# elasticNode.net
KiCad netlist of a schematic drawn in EAGLE
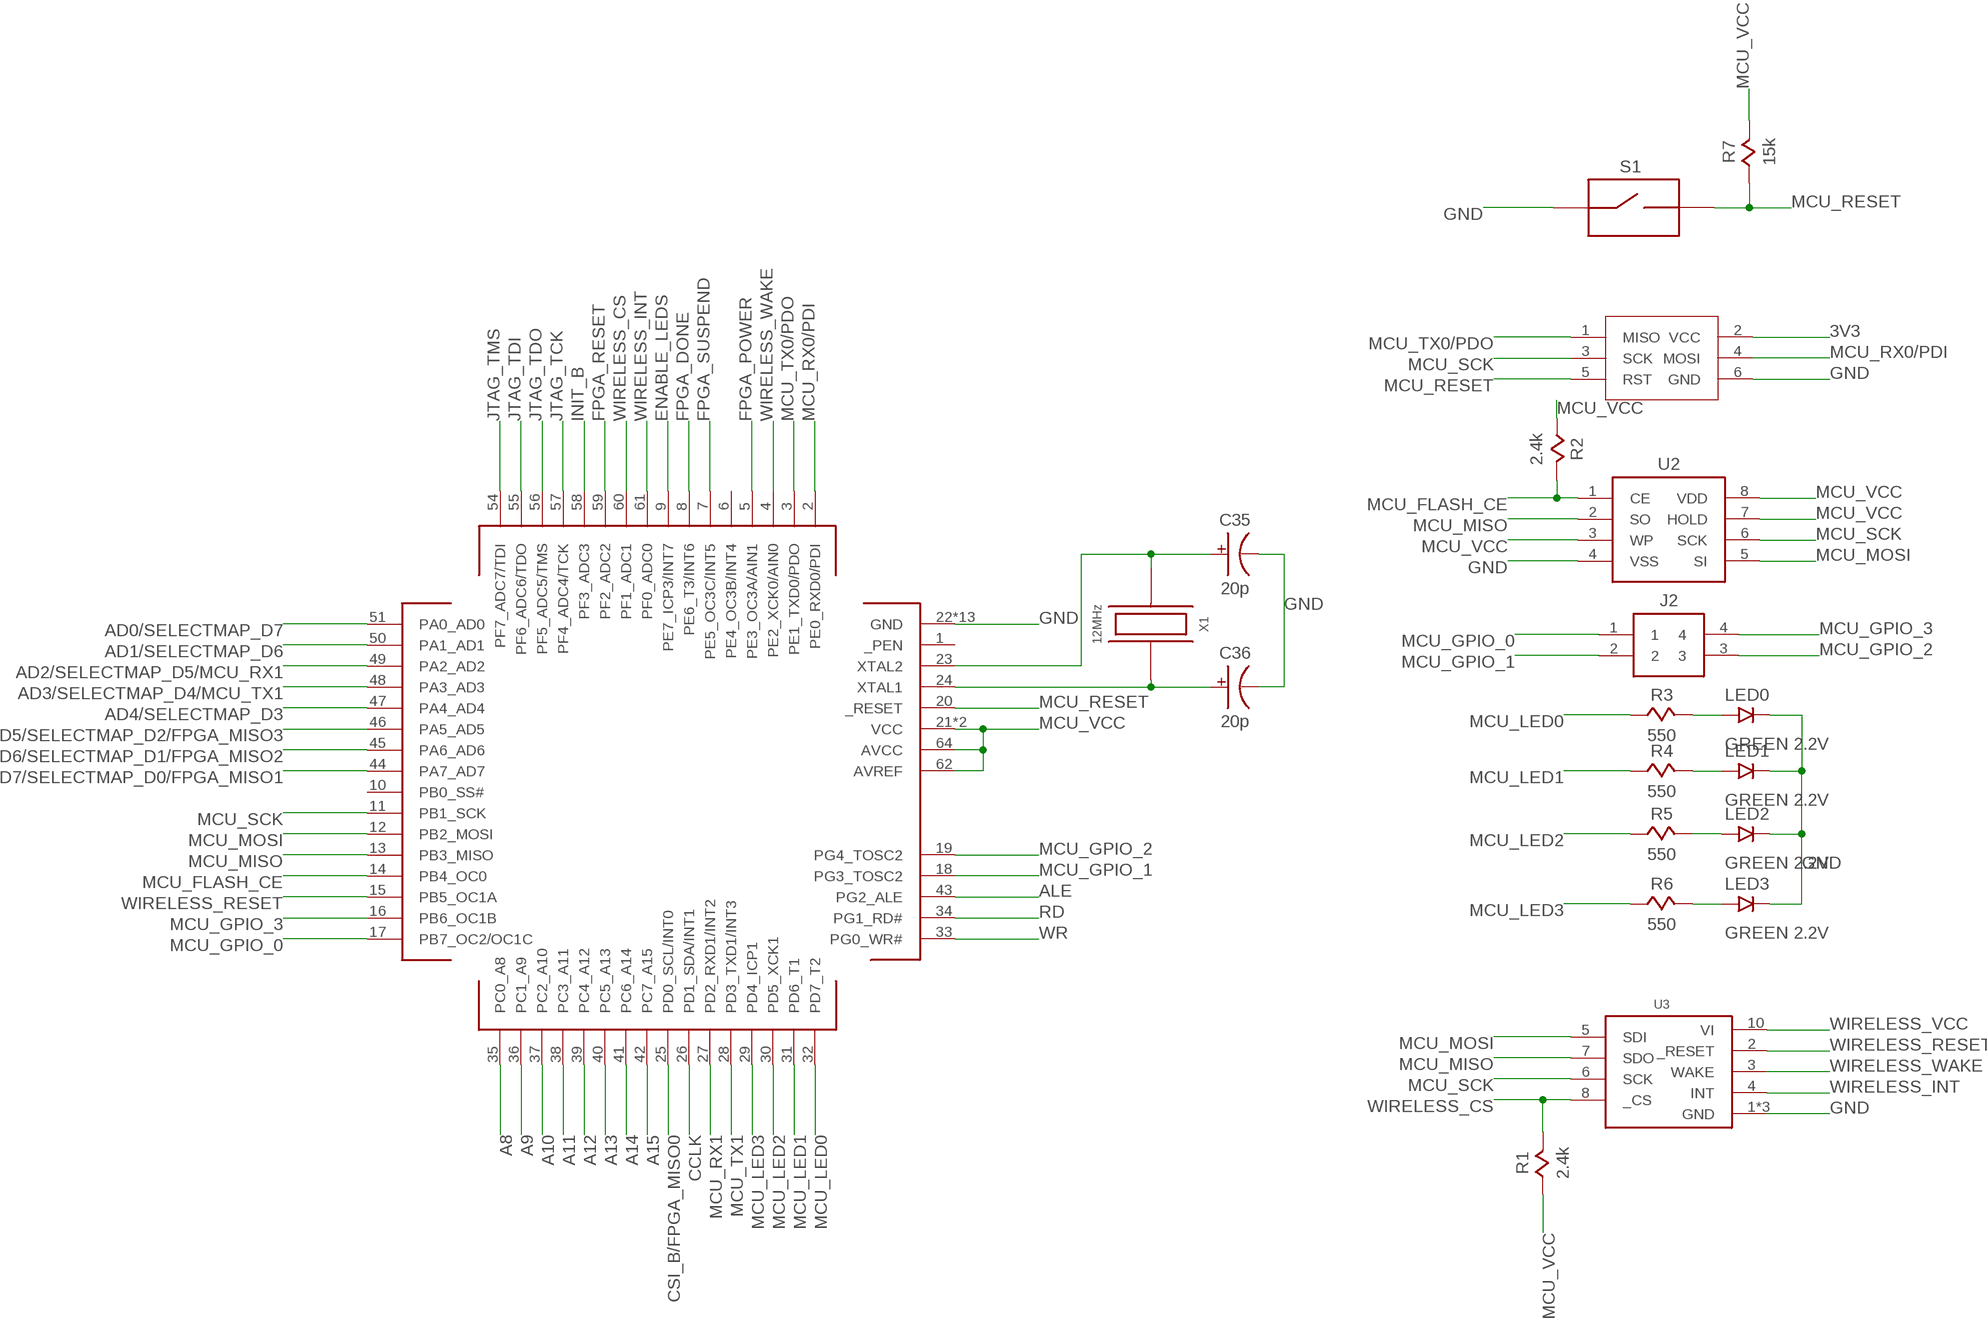
[diagram p0: schematic, sheet 1]
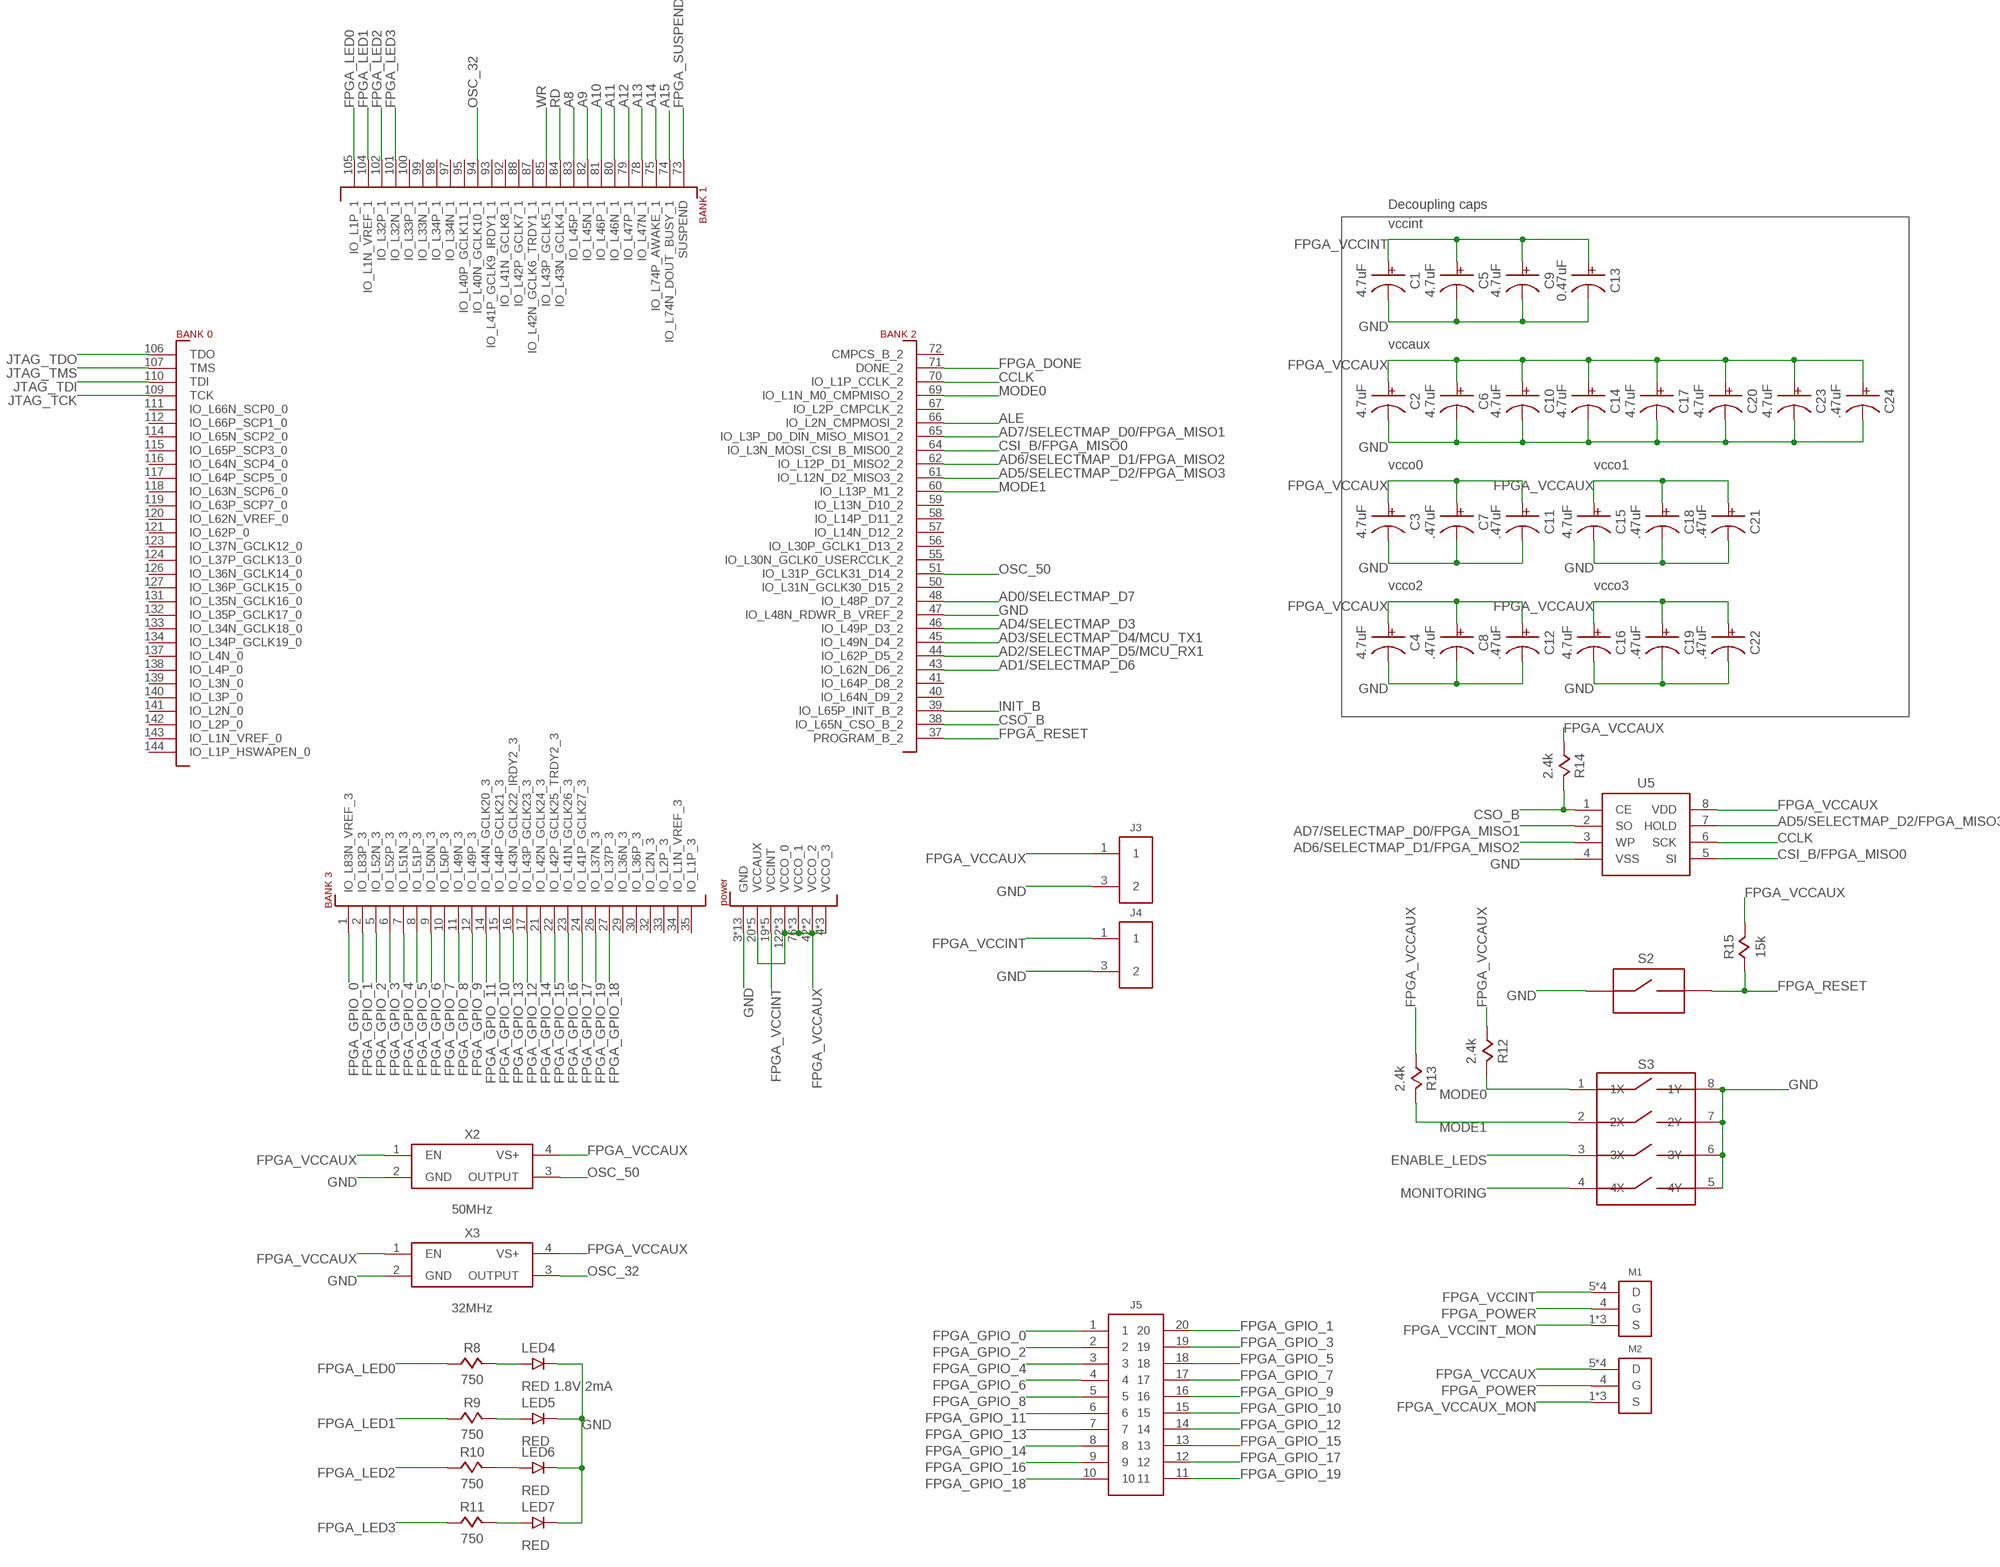
[diagram p1: schematic, sheet 2]
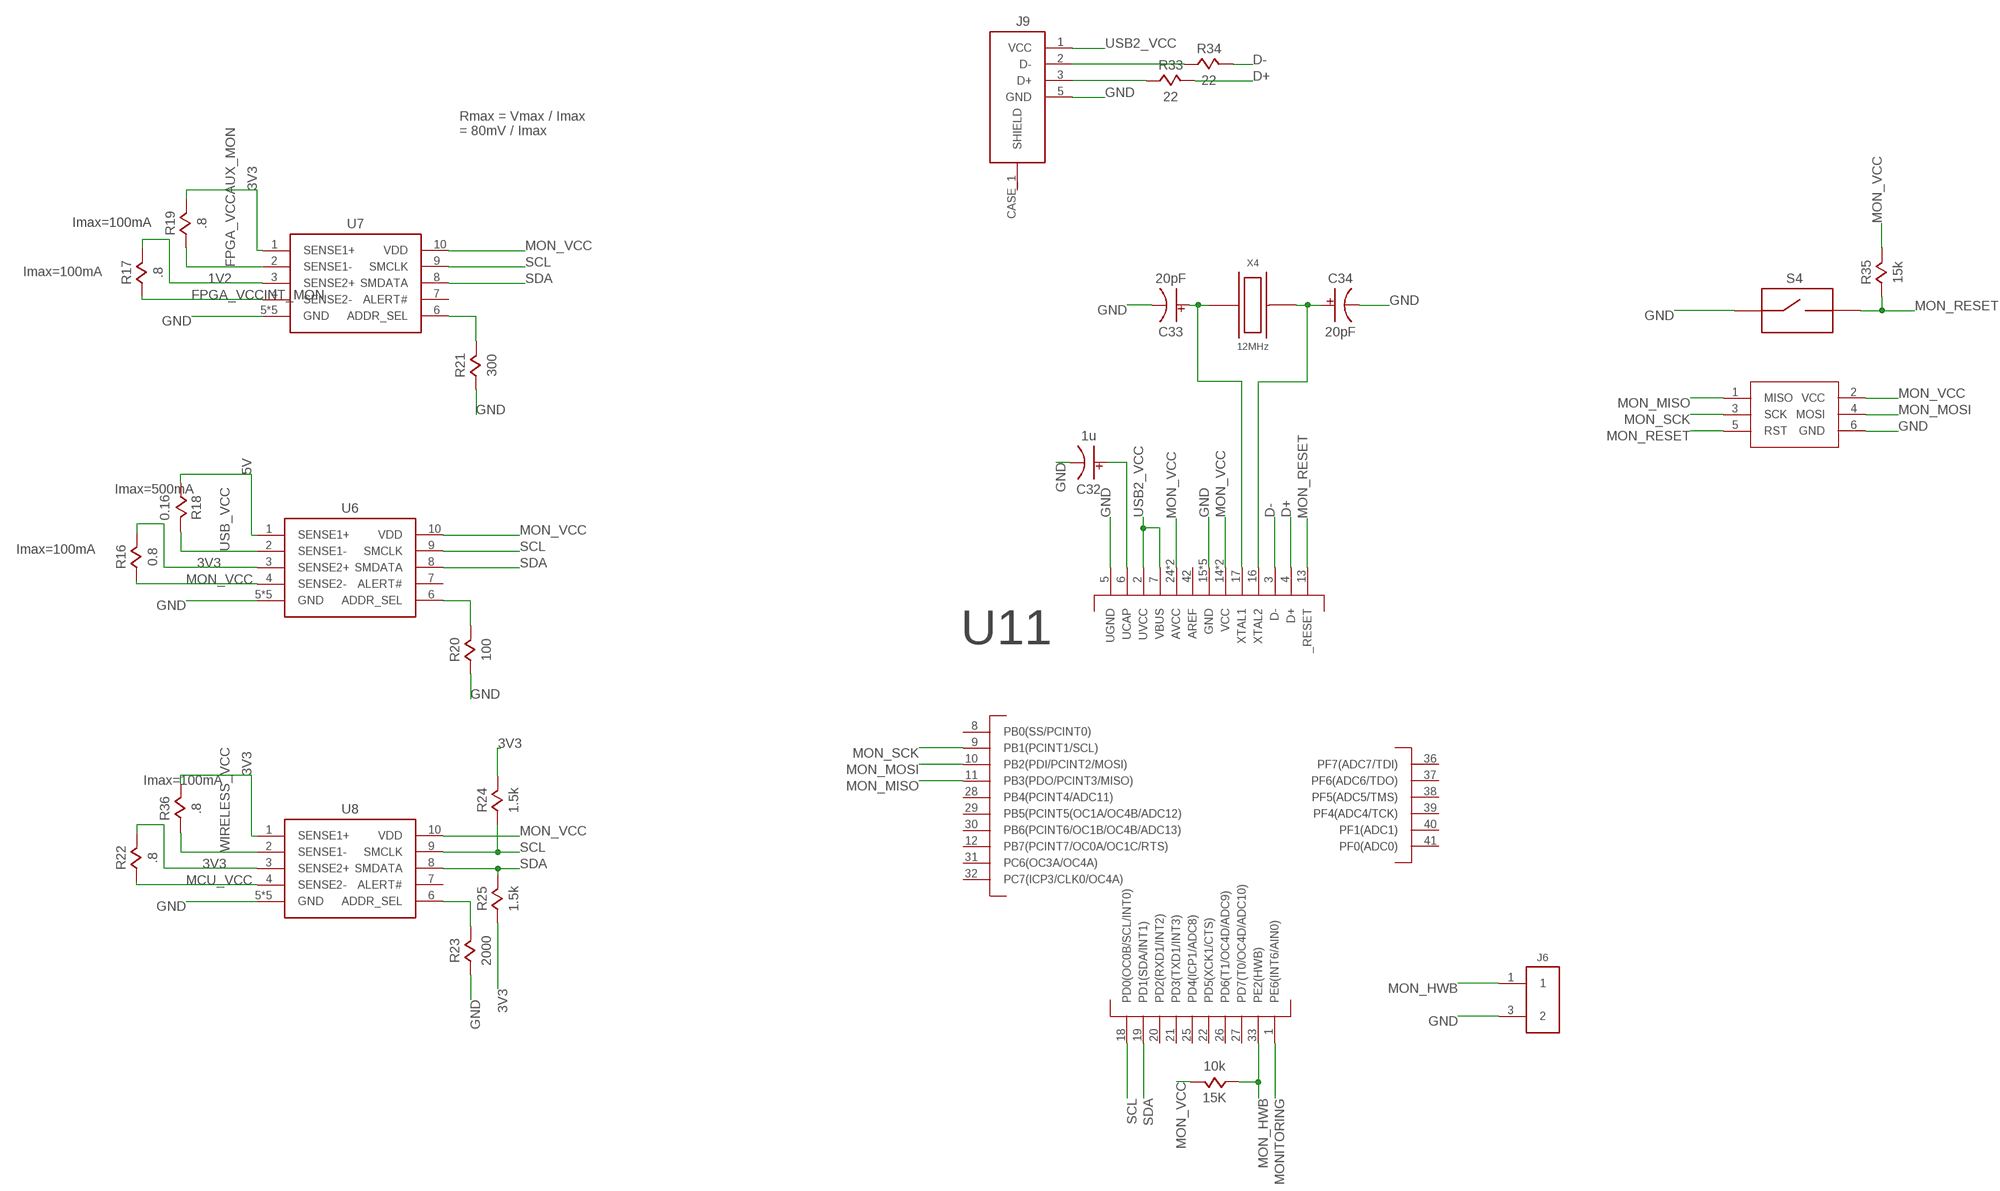
[diagram p2: schematic, sheet 3]
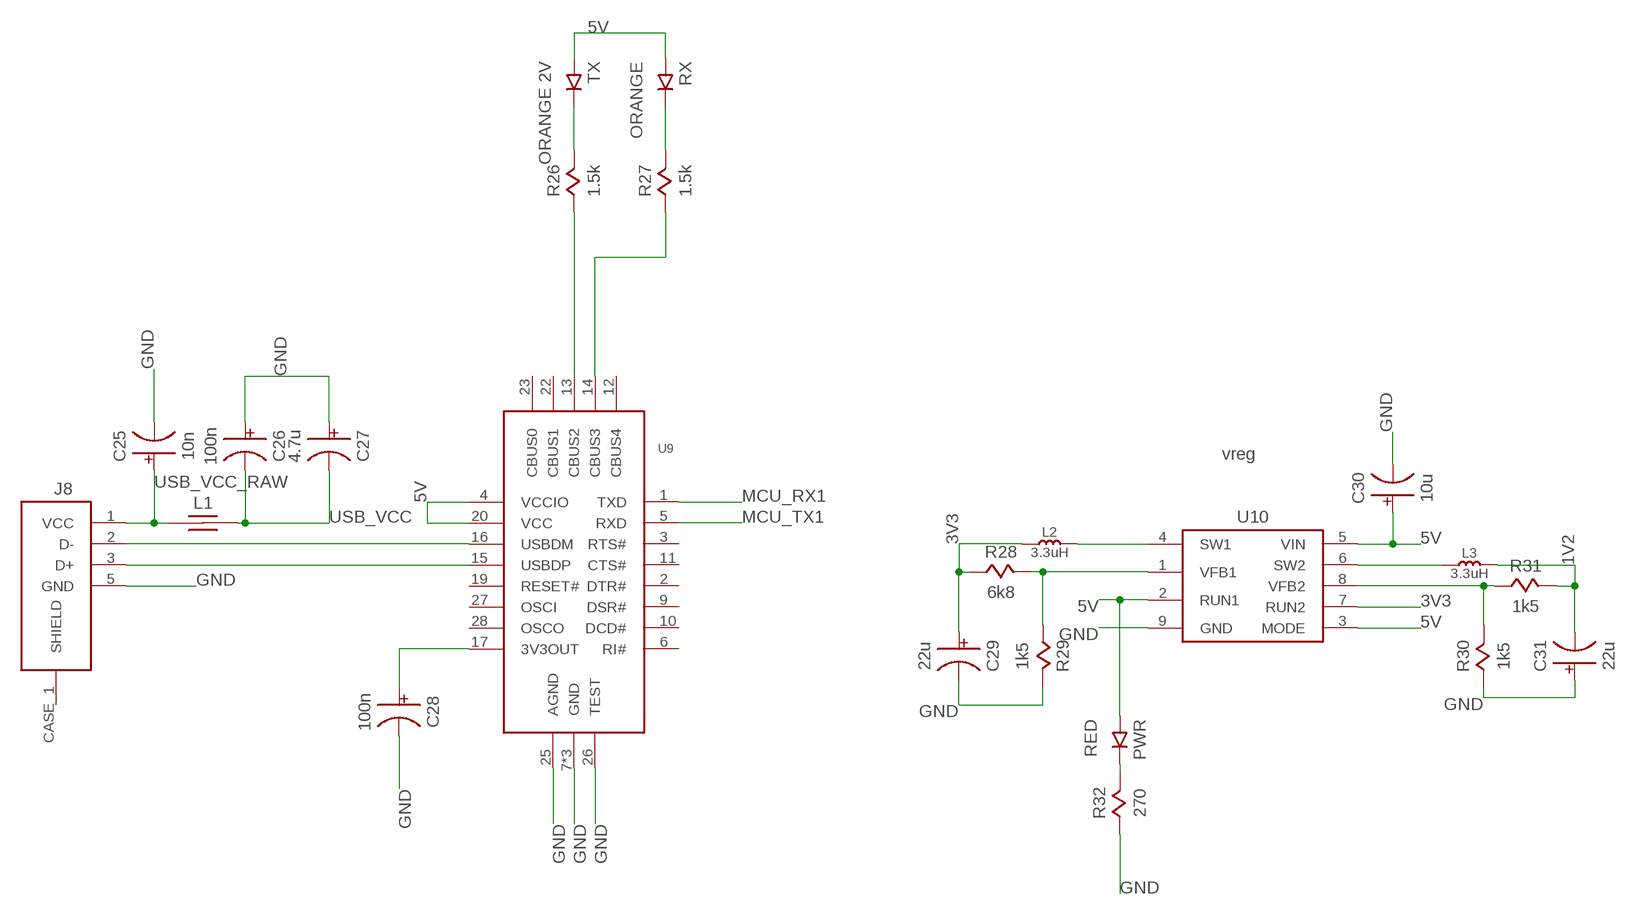
[diagram p3: schematic, sheet 4]

(export (version "E")
  (design (tool "Eeschema 10.0.6"))
  (components
    (comp (ref "15K")
      (value "10k")
      (footprint "eagle-import:0805")
      (libsource (lib "eagle-import") (part "RESISTOR"))
    )
    (comp (ref "C32")
      (value "1u")
      (footprint "eagle-import:0805")
      (libsource (lib "eagle-import") (part "CAPACITOR0805"))
    )
    (comp (ref "C33")
      (value "20pF")
      (footprint "eagle-import:0805")
      (libsource (lib "eagle-import") (part "CAPACITOR0805"))
    )
    (comp (ref "C34")
      (value "20pF")
      (footprint "eagle-import:0805")
      (libsource (lib "eagle-import") (part "CAPACITOR0805"))
    )
    (comp (ref "J6")
      (value "FEMALE_HEADER_2X1")
      (footprint "eagle-import:2X1_HEADER")
      (libsource (lib "eagle-import") (part "FEMALE_HEADER_2X1"))
    )
    (comp (ref "J9")
      (value "USB_CONNSMT")
      (footprint "eagle-import:USB_MICRO_B_SMT")
      (libsource (lib "eagle-import") (part "USB_CONNSMT"))
    )
    (comp (ref "J10")
      (value "ISP_CONN_6PIN")
      (footprint "eagle-import:3X2_HEADER_SMT")
      (libsource (lib "eagle-import") (part "ISP_CONN_6PIN"))
    )
    (comp (ref "R16")
      (value "0.8")
      (footprint "eagle-import:0805")
      (libsource (lib "eagle-import") (part "RESISTOR"))
    )
    (comp (ref "R17")
      (value ".8")
      (footprint "eagle-import:0805")
      (libsource (lib "eagle-import") (part "RESISTOR"))
    )
    (comp (ref "R18")
      (value "0.16")
      (footprint "eagle-import:0805")
      (libsource (lib "eagle-import") (part "RESISTOR"))
    )
    (comp (ref "R19")
      (value ".8")
      (footprint "eagle-import:0805")
      (libsource (lib "eagle-import") (part "RESISTOR"))
    )
    (comp (ref "R20")
      (value "100")
      (footprint "eagle-import:0805")
      (libsource (lib "eagle-import") (part "RESISTOR"))
    )
    (comp (ref "R21")
      (value "300")
      (footprint "eagle-import:0805")
      (libsource (lib "eagle-import") (part "RESISTOR"))
    )
    (comp (ref "R22")
      (value ".8")
      (footprint "eagle-import:0805")
      (libsource (lib "eagle-import") (part "RESISTOR"))
    )
    (comp (ref "R23")
      (value "2000")
      (footprint "eagle-import:0805")
      (libsource (lib "eagle-import") (part "RESISTOR"))
    )
    (comp (ref "R24")
      (value "1.5k")
      (footprint "eagle-import:0805")
      (libsource (lib "eagle-import") (part "RESISTOR"))
    )
    (comp (ref "R25")
      (value "1.5k")
      (footprint "eagle-import:0805")
      (libsource (lib "eagle-import") (part "RESISTOR"))
    )
    (comp (ref "R33")
      (value "22")
      (footprint "eagle-import:0805")
      (libsource (lib "eagle-import") (part "RESISTOR"))
    )
    (comp (ref "R34")
      (value "22")
      (footprint "eagle-import:0805")
      (libsource (lib "eagle-import") (part "RESISTOR"))
    )
    (comp (ref "R35")
      (value "15k")
      (footprint "eagle-import:0805")
      (libsource (lib "eagle-import") (part "RESISTOR"))
    )
    (comp (ref "R36")
      (value ".8")
      (footprint "eagle-import:0805")
      (libsource (lib "eagle-import") (part "RESISTOR"))
    )
    (comp (ref "S4")
      (value "SPST_BUTTON2PIN_SMT")
      (footprint "eagle-import:SPST_2PIN_SMT")
      (libsource (lib "eagle-import") (part "SPST_BUTTON2PIN_SMT"))
    )
    (comp (ref "U6")
      (value "PAC1720")
      (footprint "eagle-import:VDFN10")
      (libsource (lib "eagle-import") (part "PAC1720"))
    )
    (comp (ref "U7")
      (value "PAC1720")
      (footprint "eagle-import:VDFN10")
      (libsource (lib "eagle-import") (part "PAC1720"))
    )
    (comp (ref "U8")
      (value "PAC1720")
      (footprint "eagle-import:VDFN10")
      (libsource (lib "eagle-import") (part "PAC1720"))
    )
    (comp (ref "U11")
      (value "ATMEGA32U4")
      (footprint "eagle-import:QFN44")
      (libsource (lib "eagle-import") (part "ATMEGA32U4"))
    )
    (comp (ref "X4")
      (value "12MHz")
      (footprint "eagle-import:3.2X2.5_OSC")
      (libsource (lib "eagle-import") (part "QUARTZ"))
    )
    (comp (ref "C35")
      (value "20p")
      (footprint "eagle-import:0805")
      (libsource (lib "eagle-import") (part "CAPACITOR0805"))
    )
    (comp (ref "C36")
      (value "20p")
      (footprint "eagle-import:0805")
      (libsource (lib "eagle-import") (part "CAPACITOR0805"))
    )
    (comp (ref "J1")
      (value "ISP_CONN_6PIN")
      (footprint "eagle-import:3X2_HEADER_SMT")
      (fields (field (name "SPICEPREFIX") "X"))
      (libsource (lib "eagle-import") (part "ISP_CONN_6PIN"))
    )
    (comp (ref "J2")
      (value "FEMALE_HEADER_2X2")
      (footprint "eagle-import:2X2_HEADER")
      (libsource (lib "eagle-import") (part "FEMALE_HEADER_2X2"))
    )
    (comp (ref "LED0")
      (value "GREEN 2.2V")
      (footprint "eagle-import:0805")
      (libsource (lib "eagle-import") (part "LED"))
    )
    (comp (ref "LED1")
      (value "GREEN 2.2V")
      (footprint "eagle-import:0805")
      (libsource (lib "eagle-import") (part "LED"))
    )
    (comp (ref "LED2")
      (value "GREEN 2.2V")
      (footprint "eagle-import:0805")
      (libsource (lib "eagle-import") (part "LED"))
    )
    (comp (ref "LED3")
      (value "GREEN 2.2V")
      (footprint "eagle-import:0805")
      (libsource (lib "eagle-import") (part "LED"))
    )
    (comp (ref "R1")
      (value "2.4k")
      (footprint "eagle-import:0805")
      (libsource (lib "eagle-import") (part "RESISTOR"))
    )
    (comp (ref "R2")
      (value "2.4k")
      (footprint "eagle-import:0805")
      (libsource (lib "eagle-import") (part "RESISTOR"))
    )
    (comp (ref "R3")
      (value "550")
      (footprint "eagle-import:0805")
      (libsource (lib "eagle-import") (part "RESISTOR"))
    )
    (comp (ref "R4")
      (value "550")
      (footprint "eagle-import:0805")
      (libsource (lib "eagle-import") (part "RESISTOR"))
    )
    (comp (ref "R5")
      (value "550")
      (footprint "eagle-import:0805")
      (libsource (lib "eagle-import") (part "RESISTOR"))
    )
    (comp (ref "R6")
      (value "550")
      (footprint "eagle-import:0805")
      (libsource (lib "eagle-import") (part "RESISTOR"))
    )
    (comp (ref "R7")
      (value "15k")
      (footprint "eagle-import:0805")
      (libsource (lib "eagle-import") (part "RESISTOR"))
    )
    (comp (ref "S1")
      (value "SPST_BUTTON2PIN_SMT")
      (footprint "eagle-import:SPST_2PIN_SMT")
      (libsource (lib "eagle-import") (part "SPST_BUTTON2PIN_SMT"))
    )
    (comp (ref "U1")
      (value "ATMEGA64AQFN")
      (footprint "eagle-import:QFN64")
      (libsource (lib "eagle-import") (part "ATMEGA64AQFN"))
    )
    (comp (ref "U2")
      (value "SST26VF032B")
      (footprint "eagle-import:SOIC8")
      (libsource (lib "eagle-import") (part "SST26VF032B"))
    )
    (comp (ref "U3")
      (value "MRF24J40MA")
      (footprint "eagle-import:MRF24J40MA")
      (libsource (lib "eagle-import") (part "MRF24J40MA"))
    )
    (comp (ref "X1")
      (value "12MHz")
      (footprint "eagle-import:3.2X2.5_OSC")
      (libsource (lib "eagle-import") (part "QUARTZ"))
    )
    (comp (ref "C25")
      (value "10n")
      (footprint "eagle-import:0805")
      (libsource (lib "eagle-import") (part "CAPACITOR0805"))
    )
    (comp (ref "C26")
      (value "100n")
      (footprint "eagle-import:0805")
      (libsource (lib "eagle-import") (part "CAPACITOR0805"))
    )
    (comp (ref "C27")
      (value "4.7u")
      (footprint "eagle-import:0805")
      (libsource (lib "eagle-import") (part "CAPACITOR0805"))
    )
    (comp (ref "C28")
      (value "100n")
      (footprint "eagle-import:0805")
      (libsource (lib "eagle-import") (part "CAPACITOR0805"))
    )
    (comp (ref "C29")
      (value "22u")
      (footprint "eagle-import:0805")
      (libsource (lib "eagle-import") (part "CAPACITOR0805"))
    )
    (comp (ref "C30")
      (value "10u")
      (footprint "eagle-import:0805")
      (libsource (lib "eagle-import") (part "CAPACITOR0805"))
    )
    (comp (ref "C31")
      (value "22u")
      (footprint "eagle-import:0805")
      (libsource (lib "eagle-import") (part "CAPACITOR0805"))
    )
    (comp (ref "J8")
      (value "USB_CONNSMT")
      (footprint "eagle-import:USB_MICRO_B_SMT")
      (libsource (lib "eagle-import") (part "USB_CONNSMT"))
    )
    (comp (ref "L1")
      (value "40Ohm 1.5A")
      (footprint "eagle-import:0805")
      (libsource (lib "eagle-import") (part "FERRITE_BEAD"))
    )
    (comp (ref "L2")
      (value "3.3uH")
      (footprint "eagle-import:0805")
      (libsource (lib "eagle-import") (part "INDUCTOR"))
    )
    (comp (ref "L3")
      (value "3.3uH")
      (footprint "eagle-import:0805")
      (libsource (lib "eagle-import") (part "INDUCTOR"))
    )
    (comp (ref "PWR")
      (value "RED")
      (footprint "eagle-import:0805")
      (libsource (lib "eagle-import") (part "LED"))
    )
    (comp (ref "R26")
      (value "1.5k")
      (footprint "eagle-import:0805")
      (libsource (lib "eagle-import") (part "RESISTOR"))
    )
    (comp (ref "R27")
      (value "1.5k")
      (footprint "eagle-import:0805")
      (libsource (lib "eagle-import") (part "RESISTOR"))
    )
    (comp (ref "R28")
      (value "6k8")
      (footprint "eagle-import:0805")
      (libsource (lib "eagle-import") (part "RESISTOR"))
    )
    (comp (ref "R29")
      (value "1k5")
      (footprint "eagle-import:0805")
      (libsource (lib "eagle-import") (part "RESISTOR"))
    )
    (comp (ref "R30")
      (value "1k5")
      (footprint "eagle-import:0805")
      (libsource (lib "eagle-import") (part "RESISTOR"))
    )
    (comp (ref "R31")
      (value "1k5")
      (footprint "eagle-import:0805")
      (libsource (lib "eagle-import") (part "RESISTOR"))
    )
    (comp (ref "R32")
      (value "270")
      (footprint "eagle-import:0805")
      (libsource (lib "eagle-import") (part "RESISTOR"))
    )
    (comp (ref "RX")
      (value "ORANGE")
      (footprint "eagle-import:0805")
      (libsource (lib "eagle-import") (part "LED"))
    )
    (comp (ref "TX")
      (value "ORANGE 2V")
      (footprint "eagle-import:0805")
      (libsource (lib "eagle-import") (part "LED"))
    )
    (comp (ref "U9")
      (value "FT232RSSOP28")
      (footprint "eagle-import:SSOP28")
      (libsource (lib "eagle-import") (part "FT232RSSOP28"))
    )
    (comp (ref "U10")
      (value "LTC3419DFN")
      (footprint "eagle-import:DFN8")
      (libsource (lib "eagle-import") (part "LTC3419DFN"))
    )
    (comp (ref "C1")
      (value "4.7uF")
      (footprint "eagle-import:0805")
      (libsource (lib "eagle-import") (part "CAPACITOR0805"))
    )
    (comp (ref "C2")
      (value "4.7uF")
      (footprint "eagle-import:0805")
      (libsource (lib "eagle-import") (part "CAPACITOR0805"))
    )
    (comp (ref "C3")
      (value "4.7uF")
      (footprint "eagle-import:0805")
      (libsource (lib "eagle-import") (part "CAPACITOR0805"))
    )
    (comp (ref "C4")
      (value "4.7uF")
      (footprint "eagle-import:0805")
      (libsource (lib "eagle-import") (part "CAPACITOR0805"))
    )
    (comp (ref "C5")
      (value "4.7uF")
      (footprint "eagle-import:0805")
      (libsource (lib "eagle-import") (part "CAPACITOR0805"))
    )
    (comp (ref "C6")
      (value "4.7uF")
      (footprint "eagle-import:0805")
      (libsource (lib "eagle-import") (part "CAPACITOR0805"))
    )
    (comp (ref "C7")
      (value ".47uF")
      (footprint "eagle-import:0402")
      (libsource (lib "eagle-import") (part "CAPACITOR0402"))
    )
    (comp (ref "C8")
      (value ".47uF")
      (footprint "eagle-import:0402")
      (libsource (lib "eagle-import") (part "CAPACITOR0402"))
    )
    (comp (ref "C9")
      (value "4.7uF")
      (footprint "eagle-import:0805")
      (libsource (lib "eagle-import") (part "CAPACITOR0805"))
    )
    (comp (ref "C10")
      (value "4.7uF")
      (footprint "eagle-import:0805")
      (libsource (lib "eagle-import") (part "CAPACITOR0805"))
    )
    (comp (ref "C11")
      (value ".47uF")
      (footprint "eagle-import:0402")
      (libsource (lib "eagle-import") (part "CAPACITOR0402"))
    )
    (comp (ref "C12")
      (value ".47uF")
      (footprint "eagle-import:0402")
      (libsource (lib "eagle-import") (part "CAPACITOR0402"))
    )
    (comp (ref "C13")
      (value "0.47uF")
      (footprint "eagle-import:0402")
      (libsource (lib "eagle-import") (part "CAPACITOR0402"))
    )
    (comp (ref "C14")
      (value "4.7uF")
      (footprint "eagle-import:0805")
      (libsource (lib "eagle-import") (part "CAPACITOR0805"))
    )
    (comp (ref "C15")
      (value "4.7uF")
      (footprint "eagle-import:0805")
      (libsource (lib "eagle-import") (part "CAPACITOR0805"))
    )
    (comp (ref "C16")
      (value "4.7uF")
      (footprint "eagle-import:0805")
      (libsource (lib "eagle-import") (part "CAPACITOR0805"))
    )
    (comp (ref "C17")
      (value "4.7uF")
      (footprint "eagle-import:0805")
      (libsource (lib "eagle-import") (part "CAPACITOR0805"))
    )
    (comp (ref "C18")
      (value ".47uF")
      (footprint "eagle-import:0402")
      (libsource (lib "eagle-import") (part "CAPACITOR0402"))
    )
    (comp (ref "C19")
      (value ".47uF")
      (footprint "eagle-import:0402")
      (libsource (lib "eagle-import") (part "CAPACITOR0402"))
    )
    (comp (ref "C20")
      (value "4.7uF")
      (footprint "eagle-import:0805")
      (libsource (lib "eagle-import") (part "CAPACITOR0805"))
    )
    (comp (ref "C21")
      (value ".47uF")
      (footprint "eagle-import:0402")
      (libsource (lib "eagle-import") (part "CAPACITOR0402"))
    )
    (comp (ref "C22")
      (value ".47uF")
      (footprint "eagle-import:0402")
      (libsource (lib "eagle-import") (part "CAPACITOR0402"))
    )
    (comp (ref "C23")
      (value "4.7uF")
      (footprint "eagle-import:0805")
      (libsource (lib "eagle-import") (part "CAPACITOR0805"))
    )
    (comp (ref "C24")
      (value ".47uF")
      (footprint "eagle-import:0805")
      (libsource (lib "eagle-import") (part "CAPACITOR0805"))
    )
    (comp (ref "J3")
      (value "FEMALE_HEADER_2X1")
      (footprint "eagle-import:2X1_HEADER")
      (libsource (lib "eagle-import") (part "FEMALE_HEADER_2X1"))
    )
    (comp (ref "J4")
      (value "FEMALE_HEADER_2X1")
      (footprint "eagle-import:2X1_HEADER")
      (libsource (lib "eagle-import") (part "FEMALE_HEADER_2X1"))
    )
    (comp (ref "J5")
      (value "FEMALE_HEADER_10X2")
      (footprint "eagle-import:10X2_HEADER_SMT")
      (libsource (lib "eagle-import") (part "FEMALE_HEADER_10X2"))
    )
    (comp (ref "LED4")
      (value "RED 1.8V 2mA")
      (footprint "eagle-import:0805")
      (libsource (lib "eagle-import") (part "LED"))
    )
    (comp (ref "LED5")
      (value "RED")
      (footprint "eagle-import:0805")
      (libsource (lib "eagle-import") (part "LED"))
    )
    (comp (ref "LED6")
      (value "RED")
      (footprint "eagle-import:0805")
      (libsource (lib "eagle-import") (part "LED"))
    )
    (comp (ref "LED7")
      (value "RED")
      (footprint "eagle-import:0805")
      (libsource (lib "eagle-import") (part "LED"))
    )
    (comp (ref "M1")
      (value "SISS23DN")
      (footprint "eagle-import:POWERPAK1212-8")
      (libsource (lib "eagle-import") (part "SISS23DN"))
    )
    (comp (ref "M2")
      (value "SISS23DN")
      (footprint "eagle-import:POWERPAK1212-8")
      (libsource (lib "eagle-import") (part "SISS23DN"))
    )
    (comp (ref "R8")
      (value "750")
      (footprint "eagle-import:0805")
      (libsource (lib "eagle-import") (part "RESISTOR"))
    )
    (comp (ref "R9")
      (value "750")
      (footprint "eagle-import:0805")
      (libsource (lib "eagle-import") (part "RESISTOR"))
    )
    (comp (ref "R10")
      (value "750")
      (footprint "eagle-import:0805")
      (libsource (lib "eagle-import") (part "RESISTOR"))
    )
    (comp (ref "R11")
      (value "750")
      (footprint "eagle-import:0805")
      (libsource (lib "eagle-import") (part "RESISTOR"))
    )
    (comp (ref "R12")
      (value "2.4k")
      (footprint "eagle-import:0805")
      (libsource (lib "eagle-import") (part "RESISTOR"))
    )
    (comp (ref "R13")
      (value "2.4k")
      (footprint "eagle-import:0805")
      (libsource (lib "eagle-import") (part "RESISTOR"))
    )
    (comp (ref "R14")
      (value "2.4k")
      (footprint "eagle-import:0805")
      (libsource (lib "eagle-import") (part "RESISTOR"))
    )
    (comp (ref "R15")
      (value "15k")
      (footprint "eagle-import:0805")
      (libsource (lib "eagle-import") (part "RESISTOR"))
    )
    (comp (ref "S2")
      (value "SPST_BUTTON2PIN_SMT")
      (footprint "eagle-import:SPST_2PIN_SMT")
      (libsource (lib "eagle-import") (part "SPST_BUTTON2PIN_SMT"))
    )
    (comp (ref "S3")
      (value "SPST_DIP_4")
      (footprint "eagle-import:SPST_DIP4_SMT")
      (libsource (lib "eagle-import") (part "SPST_DIP_4"))
    )
    (comp (ref "U4")
      (value "SPARTAN6-LX9")
      (footprint "eagle-import:TQG144")
      (libsource (lib "eagle-import") (part "SPARTAN6-LX9"))
    )
    (comp (ref "U5")
      (value "SST26VF032B")
      (footprint "eagle-import:SOIC8")
      (libsource (lib "eagle-import") (part "SST26VF032B"))
    )
    (comp (ref "X2")
      (value "50MHz")
      (footprint "eagle-import:3.2X2.5_OSC")
      (libsource (lib "eagle-import") (part "OSCILLATOR3.2X2.5"))
    )
    (comp (ref "X3")
      (value "32MHz")
      (footprint "eagle-import:3.2X2.5_OSC")
      (libsource (lib "eagle-import") (part "OSCILLATOR3.2X2.5"))
    )
  )
  (nets
    (net (code "1") (name "1V2") (class "Default")
      (node (ref "C31") (pin "2") (pinfunction "P$2_2") (pintype "bidirectional"))
      (node (ref "L3") (pin "2") (pinfunction "P$2_2") (pintype "bidirectional"))
      (node (ref "R17") (pin "2") (pinfunction "2_2") (pintype "bidirectional"))
      (node (ref "R31") (pin "2") (pinfunction "2_2") (pintype "bidirectional"))
      (node (ref "U7") (pin "3") (pinfunction "SENSE2+_3") (pintype "bidirectional"))
    )
    (net (code "2") (name "3V3") (class "Default")
      (node (ref "C29") (pin "1") (pinfunction "P$1_1") (pintype "bidirectional"))
      (node (ref "J1") (pin "2") (pinfunction "VCC_2") (pintype "bidirectional"))
      (node (ref "L2") (pin "1") (pinfunction "P$1_1") (pintype "bidirectional"))
      (node (ref "R16") (pin "2") (pinfunction "2_2") (pintype "bidirectional"))
      (node (ref "R19") (pin "2") (pinfunction "2_2") (pintype "bidirectional"))
      (node (ref "R22") (pin "2") (pinfunction "2_2") (pintype "bidirectional"))
      (node (ref "R24") (pin "2") (pinfunction "2_2") (pintype "bidirectional"))
      (node (ref "R25") (pin "1") (pinfunction "1_1") (pintype "bidirectional"))
      (node (ref "R28") (pin "1") (pinfunction "1_1") (pintype "bidirectional"))
      (node (ref "R36") (pin "1") (pinfunction "1_1") (pintype "bidirectional"))
      (node (ref "U10") (pin "7") (pinfunction "RUN2_7") (pintype "bidirectional"))
      (node (ref "U6") (pin "3") (pinfunction "SENSE2+_3") (pintype "bidirectional"))
      (node (ref "U7") (pin "1") (pinfunction "SENSE1+_1") (pintype "bidirectional"))
      (node (ref "U8") (pin "1") (pinfunction "SENSE1+_1") (pintype "bidirectional"))
      (node (ref "U8") (pin "3") (pinfunction "SENSE2+_3") (pintype "bidirectional"))
    )
    (net (code "3") (name "5V") (class "Default")
      (node (ref "C30") (pin "1") (pinfunction "P$1_1") (pintype "bidirectional"))
      (node (ref "PWR") (pin "1") (pinfunction "1_1") (pintype "bidirectional"))
      (node (ref "R18") (pin "1") (pinfunction "1_1") (pintype "bidirectional"))
      (node (ref "RX") (pin "1") (pinfunction "1_1") (pintype "bidirectional"))
      (node (ref "TX") (pin "1") (pinfunction "1_1") (pintype "bidirectional"))
      (node (ref "U10") (pin "2") (pinfunction "RUN1_2") (pintype "bidirectional"))
      (node (ref "U10") (pin "3") (pinfunction "MODE_3") (pintype "bidirectional"))
      (node (ref "U10") (pin "5") (pinfunction "VIN_5") (pintype "bidirectional"))
      (node (ref "U6") (pin "1") (pinfunction "SENSE1+_1") (pintype "bidirectional"))
      (node (ref "U9") (pin "20") (pinfunction "VCC_20") (pintype "bidirectional"))
      (node (ref "U9") (pin "4") (pinfunction "VCCIO_4") (pintype "bidirectional"))
    )
    (net (code "4") (name "A8") (class "Default")
      (node (ref "U1") (pin "35") (pinfunction "PC0_A8_35") (pintype "bidirectional"))
      (node (ref "U4") (pin "83") (pinfunction "IO_L45P_1_83") (pintype "bidirectional"))
    )
    (net (code "5") (name "A9") (class "Default")
      (node (ref "U1") (pin "36") (pinfunction "PC1_A9_36") (pintype "bidirectional"))
      (node (ref "U4") (pin "82") (pinfunction "IO_L45N_1_82") (pintype "bidirectional"))
    )
    (net (code "6") (name "A10") (class "Default")
      (node (ref "U1") (pin "37") (pinfunction "PC2_A10_37") (pintype "bidirectional"))
      (node (ref "U4") (pin "81") (pinfunction "IO_L46P_1_81") (pintype "bidirectional"))
    )
    (net (code "7") (name "A11") (class "Default")
      (node (ref "U1") (pin "38") (pinfunction "PC3_A11_38") (pintype "bidirectional"))
      (node (ref "U4") (pin "80") (pinfunction "IO_L46N_1_80") (pintype "bidirectional"))
    )
    (net (code "8") (name "A12") (class "Default")
      (node (ref "U1") (pin "39") (pinfunction "PC4_A12_39") (pintype "bidirectional"))
      (node (ref "U4") (pin "79") (pinfunction "IO_L47P_1_79") (pintype "bidirectional"))
    )
    (net (code "9") (name "A13") (class "Default")
      (node (ref "U1") (pin "40") (pinfunction "PC5_A13_40") (pintype "bidirectional"))
      (node (ref "U4") (pin "78") (pinfunction "IO_L47N_1_78") (pintype "bidirectional"))
    )
    (net (code "10") (name "A14") (class "Default")
      (node (ref "U1") (pin "41") (pinfunction "PC6_A14_41") (pintype "bidirectional"))
      (node (ref "U4") (pin "75") (pinfunction "IO_L74P_AWAKE_1_75") (pintype "bidirectional"))
    )
    (net (code "11") (name "A15") (class "Default")
      (node (ref "U1") (pin "42") (pinfunction "PC7_A15_42") (pintype "bidirectional"))
      (node (ref "U4") (pin "74") (pinfunction "IO_L74N_DOUT_BUSY_1_74") (pintype "bidirectional"))
    )
    (net (code "12") (name "AD0{slash}SELECTMAP_D7") (class "Default")
      (node (ref "U1") (pin "51") (pinfunction "PA0_AD0_51") (pintype "bidirectional"))
      (node (ref "U4") (pin "48") (pinfunction "IO_L48P_D7_2_48") (pintype "bidirectional"))
    )
    (net (code "13") (name "AD1{slash}SELECTMAP_D6") (class "Default")
      (node (ref "U1") (pin "50") (pinfunction "PA1_AD1_50") (pintype "bidirectional"))
      (node (ref "U4") (pin "43") (pinfunction "IO_L62N_D6_2_43") (pintype "bidirectional"))
    )
    (net (code "14") (name "AD2{slash}SELECTMAP_D5{slash}MCU_RX1") (class "Default")
      (node (ref "U1") (pin "49") (pinfunction "PA2_AD2_49") (pintype "bidirectional"))
      (node (ref "U4") (pin "44") (pinfunction "IO_L62P_D5_2_44") (pintype "bidirectional"))
    )
    (net (code "15") (name "AD3{slash}SELECTMAP_D4{slash}MCU_TX1") (class "Default")
      (node (ref "U1") (pin "48") (pinfunction "PA3_AD3_48") (pintype "bidirectional"))
      (node (ref "U4") (pin "45") (pinfunction "IO_L49N_D4_2_45") (pintype "bidirectional"))
    )
    (net (code "16") (name "AD4{slash}SELECTMAP_D3") (class "Default")
      (node (ref "U1") (pin "47") (pinfunction "PA4_AD4_47") (pintype "bidirectional"))
      (node (ref "U4") (pin "46") (pinfunction "IO_L49P_D3_2_46") (pintype "bidirectional"))
    )
    (net (code "17") (name "AD5{slash}SELECTMAP_D2{slash}FPGA_MISO3") (class "Default")
      (node (ref "U1") (pin "46") (pinfunction "PA5_AD5_46") (pintype "bidirectional"))
      (node (ref "U4") (pin "61") (pinfunction "IO_L12N_D2_MISO3_2_61") (pintype "bidirectional"))
      (node (ref "U5") (pin "7") (pinfunction "HOLD_7") (pintype "bidirectional"))
    )
    (net (code "18") (name "AD6{slash}SELECTMAP_D1{slash}FPGA_MISO2") (class "Default")
      (node (ref "U1") (pin "45") (pinfunction "PA6_AD6_45") (pintype "bidirectional"))
      (node (ref "U4") (pin "62") (pinfunction "IO_L12P_D1_MISO2_2_62") (pintype "bidirectional"))
      (node (ref "U5") (pin "3") (pinfunction "WP_3") (pintype "bidirectional"))
    )
    (net (code "19") (name "AD7{slash}SELECTMAP_D0{slash}FPGA_MISO1") (class "Default")
      (node (ref "U1") (pin "44") (pinfunction "PA7_AD7_44") (pintype "bidirectional"))
      (node (ref "U4") (pin "65") (pinfunction "IO_L3P_D0_DIN_MISO_MISO1_2_65") (pintype "bidirectional"))
      (node (ref "U5") (pin "2") (pinfunction "SO_2") (pintype "bidirectional"))
    )
    (net (code "20") (name "ALE") (class "Default")
      (node (ref "U1") (pin "43") (pinfunction "PG2_ALE_43") (pintype "bidirectional"))
      (node (ref "U4") (pin "66") (pinfunction "IO_L2N_CMPMOSI_2_66") (pintype "bidirectional"))
    )
    (net (code "21") (name "CCLK") (class "Default")
      (node (ref "U1") (pin "26") (pinfunction "PD1_SDA/INT1_26") (pintype "bidirectional"))
      (node (ref "U4") (pin "70") (pinfunction "IO_L1P_CCLK_2_70") (pintype "bidirectional"))
      (node (ref "U5") (pin "6") (pinfunction "SCK_6") (pintype "bidirectional"))
    )
    (net (code "22") (name "CSI_B{slash}FPGA_MISO0") (class "Default")
      (node (ref "U1") (pin "25") (pinfunction "PD0_SCL/INT0_25") (pintype "bidirectional"))
      (node (ref "U4") (pin "64") (pinfunction "IO_L3N_MOSI_CSI_B_MISO0_2_64") (pintype "bidirectional"))
      (node (ref "U5") (pin "5") (pinfunction "SI_5") (pintype "bidirectional"))
    )
    (net (code "23") (name "CSO_B") (class "Default")
      (node (ref "R14") (pin "2") (pinfunction "2_2") (pintype "bidirectional"))
      (node (ref "U4") (pin "38") (pinfunction "IO_L65N_CSO_B_2_38") (pintype "bidirectional"))
      (node (ref "U5") (pin "1") (pinfunction "CE_1") (pintype "bidirectional"))
    )
    (net (code "24") (name "D+") (class "Default")
      (node (ref "R33") (pin "2") (pinfunction "2_2") (pintype "bidirectional"))
      (node (ref "U11") (pin "4") (pinfunction "D+_4") (pintype "bidirectional"))
    )
    (net (code "25") (name "D-") (class "Default")
      (node (ref "R34") (pin "2") (pinfunction "2_2") (pintype "bidirectional"))
      (node (ref "U11") (pin "3") (pinfunction "D-_3") (pintype "bidirectional"))
    )
    (net (code "26") (name "ENABLE_LEDS") (class "Default")
      (node (ref "S3") (pin "3") (pinfunction "3X_3") (pintype "bidirectional"))
      (node (ref "U1") (pin "9") (pinfunction "PE7_ICP3/INT7_9") (pintype "bidirectional"))
    )
    (net (code "27") (name "FPGA_DONE") (class "Default")
      (node (ref "U1") (pin "8") (pinfunction "PE6_T3/INT6_8") (pintype "bidirectional"))
      (node (ref "U4") (pin "71") (pinfunction "DONE_2_71") (pintype "bidirectional"))
    )
    (net (code "28") (name "FPGA_GPIO_0") (class "Default")
      (node (ref "J5") (pin "1") (pinfunction "1_1") (pintype "bidirectional"))
      (node (ref "U4") (pin "1") (pinfunction "IO_L83N_VREF_3_1") (pintype "bidirectional"))
    )
    (net (code "29") (name "FPGA_GPIO_1") (class "Default")
      (node (ref "J5") (pin "20") (pinfunction "20_20") (pintype "bidirectional"))
      (node (ref "U4") (pin "2") (pinfunction "IO_L83P_3_2") (pintype "bidirectional"))
    )
    (net (code "30") (name "FPGA_GPIO_2") (class "Default")
      (node (ref "J5") (pin "2") (pinfunction "2_2") (pintype "bidirectional"))
      (node (ref "U4") (pin "5") (pinfunction "IO_L52N_3_5") (pintype "bidirectional"))
    )
    (net (code "31") (name "FPGA_GPIO_3") (class "Default")
      (node (ref "J5") (pin "19") (pinfunction "19_19") (pintype "bidirectional"))
      (node (ref "U4") (pin "6") (pinfunction "IO_L52P_3_6") (pintype "bidirectional"))
    )
    (net (code "32") (name "FPGA_GPIO_4") (class "Default")
      (node (ref "J5") (pin "3") (pinfunction "3_3") (pintype "bidirectional"))
      (node (ref "U4") (pin "7") (pinfunction "IO_L51N_3_7") (pintype "bidirectional"))
    )
    (net (code "33") (name "FPGA_GPIO_5") (class "Default")
      (node (ref "J5") (pin "18") (pinfunction "18_18") (pintype "bidirectional"))
      (node (ref "U4") (pin "8") (pinfunction "IO_L51P_3_8") (pintype "bidirectional"))
    )
    (net (code "34") (name "FPGA_GPIO_6") (class "Default")
      (node (ref "J5") (pin "4") (pinfunction "4_4") (pintype "bidirectional"))
      (node (ref "U4") (pin "9") (pinfunction "IO_L50N_3_9") (pintype "bidirectional"))
    )
    (net (code "35") (name "FPGA_GPIO_7") (class "Default")
      (node (ref "J5") (pin "17") (pinfunction "17_17") (pintype "bidirectional"))
      (node (ref "U4") (pin "10") (pinfunction "IO_L50P_3_10") (pintype "bidirectional"))
    )
    (net (code "36") (name "FPGA_GPIO_8") (class "Default")
      (node (ref "J5") (pin "5") (pinfunction "5_5") (pintype "bidirectional"))
      (node (ref "U4") (pin "11") (pinfunction "IO_L49N_3_11") (pintype "bidirectional"))
    )
    (net (code "37") (name "FPGA_GPIO_9") (class "Default")
      (node (ref "J5") (pin "16") (pinfunction "16_16") (pintype "bidirectional"))
      (node (ref "U4") (pin "12") (pinfunction "IO_L49P_3_12") (pintype "bidirectional"))
    )
    (net (code "38") (name "FPGA_GPIO_10") (class "Default")
      (node (ref "J5") (pin "15") (pinfunction "15_15") (pintype "bidirectional"))
      (node (ref "U4") (pin "15") (pinfunction "IO_L44P_GCLK21_3_15") (pintype "bidirectional"))
    )
    (net (code "39") (name "FPGA_GPIO_11") (class "Default")
      (node (ref "J5") (pin "6") (pinfunction "6_6") (pintype "bidirectional"))
      (node (ref "U4") (pin "14") (pinfunction "IO_L44N_GCLK20_3_14") (pintype "bidirectional"))
    )
    (net (code "40") (name "FPGA_GPIO_12") (class "Default")
      (node (ref "J5") (pin "14") (pinfunction "14_14") (pintype "bidirectional"))
      (node (ref "U4") (pin "17") (pinfunction "IO_L43P_GCLK23_3_17") (pintype "bidirectional"))
    )
    (net (code "41") (name "FPGA_GPIO_13") (class "Default")
      (node (ref "J5") (pin "7") (pinfunction "7_7") (pintype "bidirectional"))
      (node (ref "U4") (pin "16") (pinfunction "IO_L43N_GCLK22_IRDY2_3_16") (pintype "bidirectional"))
    )
    (net (code "42") (name "FPGA_GPIO_14") (class "Default")
      (node (ref "J5") (pin "8") (pinfunction "8_8") (pintype "bidirectional"))
      (node (ref "U4") (pin "21") (pinfunction "IO_L42N_GCLK24_3_21") (pintype "bidirectional"))
    )
    (net (code "43") (name "FPGA_GPIO_15") (class "Default")
      (node (ref "J5") (pin "13") (pinfunction "13_13") (pintype "bidirectional"))
      (node (ref "U4") (pin "22") (pinfunction "IO_L42P_GCLK25_TRDY2_3_22") (pintype "bidirectional"))
    )
    (net (code "44") (name "FPGA_GPIO_16") (class "Default")
      (node (ref "J5") (pin "9") (pinfunction "9_9") (pintype "bidirectional"))
      (node (ref "U4") (pin "23") (pinfunction "IO_L41N_GCLK26_3_23") (pintype "bidirectional"))
    )
    (net (code "45") (name "FPGA_GPIO_17") (class "Default")
      (node (ref "J5") (pin "12") (pinfunction "12_12") (pintype "bidirectional"))
      (node (ref "U4") (pin "24") (pinfunction "IO_L41P_GCLK27_3_24") (pintype "bidirectional"))
    )
    (net (code "46") (name "FPGA_GPIO_18") (class "Default")
      (node (ref "J5") (pin "10") (pinfunction "10_10") (pintype "bidirectional"))
      (node (ref "U4") (pin "27") (pinfunction "IO_L37P_3_27") (pintype "bidirectional"))
    )
    (net (code "47") (name "FPGA_GPIO_19") (class "Default")
      (node (ref "J5") (pin "11") (pinfunction "11_11") (pintype "bidirectional"))
      (node (ref "U4") (pin "26") (pinfunction "IO_L37N_3_26") (pintype "bidirectional"))
    )
    (net (code "48") (name "FPGA_LED0") (class "Default")
      (node (ref "R8") (pin "1") (pinfunction "1_1") (pintype "bidirectional"))
      (node (ref "U4") (pin "105") (pinfunction "IO_L1P_1_105") (pintype "bidirectional"))
    )
    (net (code "49") (name "FPGA_LED1") (class "Default")
      (node (ref "R9") (pin "1") (pinfunction "1_1") (pintype "bidirectional"))
      (node (ref "U4") (pin "104") (pinfunction "IO_L1N_VREF_1_104") (pintype "bidirectional"))
    )
    (net (code "50") (name "FPGA_LED2") (class "Default")
      (node (ref "R10") (pin "1") (pinfunction "1_1") (pintype "bidirectional"))
      (node (ref "U4") (pin "102") (pinfunction "IO_L32P_1_102") (pintype "bidirectional"))
    )
    (net (code "51") (name "FPGA_LED3") (class "Default")
      (node (ref "R11") (pin "1") (pinfunction "1_1") (pintype "bidirectional"))
      (node (ref "U4") (pin "101") (pinfunction "IO_L32N_1_101") (pintype "bidirectional"))
    )
    (net (code "52") (name "FPGA_POWER") (class "Default")
      (node (ref "M1") (pin "4") (pinfunction "G_4") (pintype "bidirectional"))
      (node (ref "M2") (pin "4") (pinfunction "G_4") (pintype "bidirectional"))
      (node (ref "U1") (pin "5") (pinfunction "PE3_OC3A/AIN1_5") (pintype "bidirectional"))
    )
    (net (code "53") (name "FPGA_RESET") (class "Default")
      (node (ref "R15") (pin "1") (pinfunction "1_1") (pintype "bidirectional"))
      (node (ref "S2") (pin "2") (pinfunction "3_2") (pintype "bidirectional"))
      (node (ref "U1") (pin "59") (pinfunction "PF2_ADC2_59") (pintype "bidirectional"))
      (node (ref "U4") (pin "37") (pinfunction "PROGRAM_B_2_37") (pintype "bidirectional"))
    )
    (net (code "54") (name "FPGA_SUSPEND") (class "Default")
      (node (ref "U1") (pin "7") (pinfunction "PE5_OC3C/INT5_7") (pintype "bidirectional"))
      (node (ref "U4") (pin "73") (pinfunction "SUSPEND_73") (pintype "bidirectional"))
    )
    (net (code "55") (name "FPGA_VCCAUX") (class "Default")
      (node (ref "C10") (pin "1") (pinfunction "P$1_1") (pintype "bidirectional"))
      (node (ref "C11") (pin "1") (pinfunction "P$1_1") (pintype "bidirectional"))
      (node (ref "C12") (pin "1") (pinfunction "P$1_1") (pintype "bidirectional"))
      (node (ref "C14") (pin "1") (pinfunction "P$1_1") (pintype "bidirectional"))
      (node (ref "C15") (pin "1") (pinfunction "P$1_1") (pintype "bidirectional"))
      (node (ref "C16") (pin "1") (pinfunction "P$1_1") (pintype "bidirectional"))
      (node (ref "C17") (pin "1") (pinfunction "P$1_1") (pintype "bidirectional"))
      (node (ref "C18") (pin "1") (pinfunction "P$1_1") (pintype "bidirectional"))
      (node (ref "C19") (pin "1") (pinfunction "P$1_1") (pintype "bidirectional"))
      (node (ref "C2") (pin "1") (pinfunction "P$1_1") (pintype "bidirectional"))
      (node (ref "C20") (pin "1") (pinfunction "P$1_1") (pintype "bidirectional"))
      (node (ref "C21") (pin "1") (pinfunction "P$1_1") (pintype "bidirectional"))
      (node (ref "C22") (pin "1") (pinfunction "P$1_1") (pintype "bidirectional"))
      (node (ref "C23") (pin "1") (pinfunction "P$1_1") (pintype "bidirectional"))
      (node (ref "C24") (pin "1") (pinfunction "P$1_1") (pintype "bidirectional"))
      (node (ref "C3") (pin "1") (pinfunction "P$1_1") (pintype "bidirectional"))
      (node (ref "C4") (pin "1") (pinfunction "P$1_1") (pintype "bidirectional"))
      (node (ref "C6") (pin "1") (pinfunction "P$1_1") (pintype "bidirectional"))
      (node (ref "C7") (pin "1") (pinfunction "P$1_1") (pintype "bidirectional"))
      (node (ref "C8") (pin "1") (pinfunction "P$1_1") (pintype "bidirectional"))
      (node (ref "J3") (pin "1") (pinfunction "1_1") (pintype "bidirectional"))
      (node (ref "M2") (pin "5") (pinfunction "D_5") (pintype "bidirectional"))
      (node (ref "M2") (pin "6") (pinfunction "D_6") (pintype "bidirectional"))
      (node (ref "M2") (pin "7") (pinfunction "D_7") (pintype "bidirectional"))
      (node (ref "M2") (pin "8") (pinfunction "D_8") (pintype "bidirectional"))
      (node (ref "R12") (pin "1") (pinfunction "1_1") (pintype "bidirectional"))
      (node (ref "R13") (pin "1") (pinfunction "1_1") (pintype "bidirectional"))
      (node (ref "R14") (pin "1") (pinfunction "1_1") (pintype "bidirectional"))
      (node (ref "R15") (pin "2") (pinfunction "2_2") (pintype "bidirectional"))
      (node (ref "U4") (pin "103") (pinfunction "VCCO_1_103") (pintype "bidirectional"))
      (node (ref "U4") (pin "122") (pinfunction "VCCO_0_122") (pintype "bidirectional"))
      (node (ref "U4") (pin "125") (pinfunction "VCCO_0_125") (pintype "bidirectional"))
      (node (ref "U4") (pin "129") (pinfunction "VCCAUX_129") (pintype "bidirectional"))
      (node (ref "U4") (pin "135") (pinfunction "VCCO_0_135") (pintype "bidirectional"))
      (node (ref "U4") (pin "18") (pinfunction "VCCO_3_18") (pintype "bidirectional"))
      (node (ref "U4") (pin "20") (pinfunction "VCCAUX_20") (pintype "bidirectional"))
      (node (ref "U4") (pin "31") (pinfunction "VCCO_3_31") (pintype "bidirectional"))
      (node (ref "U4") (pin "36") (pinfunction "VCCAUX_36") (pintype "bidirectional"))
      (node (ref "U4") (pin "4") (pinfunction "VCCO_3_4") (pintype "bidirectional"))
      (node (ref "U4") (pin "42") (pinfunction "VCCO_2_42") (pintype "bidirectional"))
      (node (ref "U4") (pin "53") (pinfunction "VCCAUX_53") (pintype "bidirectional"))
      (node (ref "U4") (pin "63") (pinfunction "VCCO_2_63") (pintype "bidirectional"))
      (node (ref "U4") (pin "76") (pinfunction "VCCO_1_76") (pintype "bidirectional"))
      (node (ref "U4") (pin "86") (pinfunction "VCCO_1_86") (pintype "bidirectional"))
      (node (ref "U4") (pin "90") (pinfunction "VCCAUX_90") (pintype "bidirectional"))
      (node (ref "U5") (pin "8") (pinfunction "VDD_8") (pintype "bidirectional"))
      (node (ref "X2") (pin "1") (pinfunction "EN_1") (pintype "bidirectional"))
      (node (ref "X2") (pin "4") (pinfunction "VS+_4") (pintype "bidirectional"))
      (node (ref "X3") (pin "1") (pinfunction "EN_1") (pintype "bidirectional"))
      (node (ref "X3") (pin "4") (pinfunction "VS+_4") (pintype "bidirectional"))
    )
    (net (code "56") (name "FPGA_VCCAUX_MON") (class "Default")
      (node (ref "M2") (pin "1") (pinfunction "S_1") (pintype "bidirectional"))
      (node (ref "M2") (pin "2") (pinfunction "S_2") (pintype "bidirectional"))
      (node (ref "M2") (pin "3") (pinfunction "S_3") (pintype "bidirectional"))
      (node (ref "R19") (pin "1") (pinfunction "1_1") (pintype "bidirectional"))
      (node (ref "U7") (pin "2") (pinfunction "SENSE1-_2") (pintype "bidirectional"))
    )
    (net (code "57") (name "FPGA_VCCINT") (class "Default")
      (node (ref "C1") (pin "1") (pinfunction "P$1_1") (pintype "bidirectional"))
      (node (ref "C13") (pin "1") (pinfunction "P$1_1") (pintype "bidirectional"))
      (node (ref "C5") (pin "1") (pinfunction "P$1_1") (pintype "bidirectional"))
      (node (ref "C9") (pin "1") (pinfunction "P$1_1") (pintype "bidirectional"))
      (node (ref "J4") (pin "1") (pinfunction "1_1") (pintype "bidirectional"))
      (node (ref "M1") (pin "5") (pinfunction "D_5") (pintype "bidirectional"))
      (node (ref "M1") (pin "6") (pinfunction "D_6") (pintype "bidirectional"))
      (node (ref "M1") (pin "7") (pinfunction "D_7") (pintype "bidirectional"))
      (node (ref "M1") (pin "8") (pinfunction "D_8") (pintype "bidirectional"))
      (node (ref "U4") (pin "128") (pinfunction "VCCINT_128") (pintype "bidirectional"))
      (node (ref "U4") (pin "19") (pinfunction "VCCINT_19") (pintype "bidirectional"))
      (node (ref "U4") (pin "28") (pinfunction "VCCINT_28") (pintype "bidirectional"))
      (node (ref "U4") (pin "52") (pinfunction "VCCINT_52") (pintype "bidirectional"))
      (node (ref "U4") (pin "89") (pinfunction "VCCINT_89") (pintype "bidirectional"))
    )
    (net (code "58") (name "FPGA_VCCINT_MON") (class "Default")
      (node (ref "M1") (pin "1") (pinfunction "S_1") (pintype "bidirectional"))
      (node (ref "M1") (pin "2") (pinfunction "S_2") (pintype "bidirectional"))
      (node (ref "M1") (pin "3") (pinfunction "S_3") (pintype "bidirectional"))
      (node (ref "R17") (pin "1") (pinfunction "1_1") (pintype "bidirectional"))
      (node (ref "U7") (pin "4") (pinfunction "SENSE2-_4") (pintype "bidirectional"))
    )
    (net (code "59") (name "GND") (class "Default")
      (node (ref "C1") (pin "2") (pinfunction "P$2_2") (pintype "bidirectional"))
      (node (ref "C10") (pin "2") (pinfunction "P$2_2") (pintype "bidirectional"))
      (node (ref "C11") (pin "2") (pinfunction "P$2_2") (pintype "bidirectional"))
      (node (ref "C12") (pin "2") (pinfunction "P$2_2") (pintype "bidirectional"))
      (node (ref "C13") (pin "2") (pinfunction "P$2_2") (pintype "bidirectional"))
      (node (ref "C14") (pin "2") (pinfunction "P$2_2") (pintype "bidirectional"))
      (node (ref "C15") (pin "2") (pinfunction "P$2_2") (pintype "bidirectional"))
      (node (ref "C16") (pin "2") (pinfunction "P$2_2") (pintype "bidirectional"))
      (node (ref "C17") (pin "2") (pinfunction "P$2_2") (pintype "bidirectional"))
      (node (ref "C18") (pin "2") (pinfunction "P$2_2") (pintype "bidirectional"))
      (node (ref "C19") (pin "2") (pinfunction "P$2_2") (pintype "bidirectional"))
      (node (ref "C2") (pin "2") (pinfunction "P$2_2") (pintype "bidirectional"))
      (node (ref "C20") (pin "2") (pinfunction "P$2_2") (pintype "bidirectional"))
      (node (ref "C21") (pin "2") (pinfunction "P$2_2") (pintype "bidirectional"))
      (node (ref "C22") (pin "2") (pinfunction "P$2_2") (pintype "bidirectional"))
      (node (ref "C23") (pin "2") (pinfunction "P$2_2") (pintype "bidirectional"))
      (node (ref "C24") (pin "2") (pinfunction "P$2_2") (pintype "bidirectional"))
      (node (ref "C25") (pin "2") (pinfunction "P$2_2") (pintype "bidirectional"))
      (node (ref "C26") (pin "1") (pinfunction "P$1_1") (pintype "bidirectional"))
      (node (ref "C27") (pin "1") (pinfunction "P$1_1") (pintype "bidirectional"))
      (node (ref "C28") (pin "2") (pinfunction "P$2_2") (pintype "bidirectional"))
      (node (ref "C29") (pin "2") (pinfunction "P$2_2") (pintype "bidirectional"))
      (node (ref "C3") (pin "2") (pinfunction "P$2_2") (pintype "bidirectional"))
      (node (ref "C30") (pin "2") (pinfunction "P$2_2") (pintype "bidirectional"))
      (node (ref "C31") (pin "1") (pinfunction "P$1_1") (pintype "bidirectional"))
      (node (ref "C32") (pin "2") (pinfunction "P$2_2") (pintype "bidirectional"))
      (node (ref "C33") (pin "2") (pinfunction "P$2_2") (pintype "bidirectional"))
      (node (ref "C34") (pin "2") (pinfunction "P$2_2") (pintype "bidirectional"))
      (node (ref "C35") (pin "2") (pinfunction "P$2_2") (pintype "bidirectional"))
      (node (ref "C36") (pin "2") (pinfunction "P$2_2") (pintype "bidirectional"))
      (node (ref "C4") (pin "2") (pinfunction "P$2_2") (pintype "bidirectional"))
      (node (ref "C5") (pin "2") (pinfunction "P$2_2") (pintype "bidirectional"))
      (node (ref "C6") (pin "2") (pinfunction "P$2_2") (pintype "bidirectional"))
      (node (ref "C7") (pin "2") (pinfunction "P$2_2") (pintype "bidirectional"))
      (node (ref "C8") (pin "2") (pinfunction "P$2_2") (pintype "bidirectional"))
      (node (ref "C9") (pin "2") (pinfunction "P$2_2") (pintype "bidirectional"))
      (node (ref "J1") (pin "6") (pinfunction "GND_6") (pintype "bidirectional"))
      (node (ref "J10") (pin "6") (pinfunction "GND_6") (pintype "bidirectional"))
      (node (ref "J3") (pin "3") (pinfunction "2_3") (pintype "bidirectional"))
      (node (ref "J4") (pin "3") (pinfunction "2_3") (pintype "bidirectional"))
      (node (ref "J6") (pin "3") (pinfunction "2_3") (pintype "bidirectional"))
      (node (ref "J8") (pin "5") (pinfunction "GND_5") (pintype "bidirectional"))
      (node (ref "J9") (pin "5") (pinfunction "GND_5") (pintype "bidirectional"))
      (node (ref "LED0") (pin "2") (pinfunction "2_2") (pintype "bidirectional"))
      (node (ref "LED1") (pin "2") (pinfunction "2_2") (pintype "bidirectional"))
      (node (ref "LED2") (pin "2") (pinfunction "2_2") (pintype "bidirectional"))
      (node (ref "LED3") (pin "2") (pinfunction "2_2") (pintype "bidirectional"))
      (node (ref "LED4") (pin "2") (pinfunction "2_2") (pintype "bidirectional"))
      (node (ref "LED5") (pin "2") (pinfunction "2_2") (pintype "bidirectional"))
      (node (ref "LED6") (pin "2") (pinfunction "2_2") (pintype "bidirectional"))
      (node (ref "LED7") (pin "2") (pinfunction "2_2") (pintype "bidirectional"))
      (node (ref "R20") (pin "1") (pinfunction "1_1") (pintype "bidirectional"))
      (node (ref "R21") (pin "1") (pinfunction "1_1") (pintype "bidirectional"))
      (node (ref "R23") (pin "1") (pinfunction "1_1") (pintype "bidirectional"))
      (node (ref "R29") (pin "2") (pinfunction "2_2") (pintype "bidirectional"))
      (node (ref "R30") (pin "1") (pinfunction "1_1") (pintype "bidirectional"))
      (node (ref "R32") (pin "1") (pinfunction "1_1") (pintype "bidirectional"))
      (node (ref "S1") (pin "1") (pinfunction "1_1") (pintype "bidirectional"))
      (node (ref "S2") (pin "1") (pinfunction "1_1") (pintype "bidirectional"))
      (node (ref "S3") (pin "5") (pinfunction "4Y_5") (pintype "bidirectional"))
      (node (ref "S3") (pin "6") (pinfunction "3Y_6") (pintype "bidirectional"))
      (node (ref "S3") (pin "7") (pinfunction "2Y_7") (pintype "bidirectional"))
      (node (ref "S3") (pin "8") (pinfunction "1Y_8") (pintype "bidirectional"))
      (node (ref "S4") (pin "1") (pinfunction "1_1") (pintype "bidirectional"))
      (node (ref "U1") (pin "22") (pinfunction "GND_22") (pintype "bidirectional"))
      (node (ref "U1") (pin "53") (pinfunction "GND_53") (pintype "bidirectional"))
      (node (ref "U1") (pin "63") (pinfunction "GND_63") (pintype "bidirectional"))
      (node (ref "U1") (pin "PAD") (pinfunction "GND_PAD") (pintype "bidirectional"))
      (node (ref "U1") (pin "VIA1") (pinfunction "GND_VIA1") (pintype "bidirectional"))
      (node (ref "U1") (pin "VIA2") (pinfunction "GND_VIA2") (pintype "bidirectional"))
      (node (ref "U1") (pin "VIA3") (pinfunction "GND_VIA3") (pintype "bidirectional"))
      (node (ref "U1") (pin "VIA4") (pinfunction "GND_VIA4") (pintype "bidirectional"))
      (node (ref "U1") (pin "VIA5") (pinfunction "GND_VIA5") (pintype "bidirectional"))
      (node (ref "U1") (pin "VIA6") (pinfunction "GND_VIA6") (pintype "bidirectional"))
      (node (ref "U1") (pin "VIA7") (pinfunction "GND_VIA7") (pintype "bidirectional"))
      (node (ref "U1") (pin "VIA8") (pinfunction "GND_VIA8") (pintype "bidirectional"))
      (node (ref "U1") (pin "VIA9") (pinfunction "GND_VIA9") (pintype "bidirectional"))
      (node (ref "U10") (pin "9") (pinfunction "GND_9") (pintype "bidirectional"))
      (node (ref "U11") (pin "15") (pinfunction "GND_15") (pintype "bidirectional"))
      (node (ref "U11") (pin "23") (pinfunction "GND_23") (pintype "bidirectional"))
      (node (ref "U11") (pin "35") (pinfunction "GND_35") (pintype "bidirectional"))
      (node (ref "U11") (pin "43") (pinfunction "GND_43") (pintype "bidirectional"))
      (node (ref "U11") (pin "45") (pinfunction "GND_45") (pintype "bidirectional"))
      (node (ref "U11") (pin "5") (pinfunction "UGND_5") (pintype "bidirectional"))
      (node (ref "U2") (pin "4") (pinfunction "VSS_4") (pintype "bidirectional"))
      (node (ref "U3") (pin "1") (pinfunction "GND_1") (pintype "bidirectional"))
      (node (ref "U3") (pin "11") (pinfunction "GND_11") (pintype "bidirectional"))
      (node (ref "U3") (pin "12") (pinfunction "GND_12") (pintype "bidirectional"))
      (node (ref "U4") (pin "108") (pinfunction "GND_108") (pintype "bidirectional"))
      (node (ref "U4") (pin "113") (pinfunction "GND_113") (pintype "bidirectional"))
      (node (ref "U4") (pin "13") (pinfunction "GND_13") (pintype "bidirectional"))
      (node (ref "U4") (pin "130") (pinfunction "GND_130") (pintype "bidirectional"))
      (node (ref "U4") (pin "136") (pinfunction "GND_136") (pintype "bidirectional"))
      (node (ref "U4") (pin "25") (pinfunction "GND_25") (pintype "bidirectional"))
      (node (ref "U4") (pin "3") (pinfunction "GND_3") (pintype "bidirectional"))
      (node (ref "U4") (pin "47") (pinfunction "IO_L48N_RDWR_B_VREF_2_47") (pintype "bidirectional"))
      (node (ref "U4") (pin "49") (pinfunction "GND_49") (pintype "bidirectional"))
      (node (ref "U4") (pin "54") (pinfunction "GND_54") (pintype "bidirectional"))
      (node (ref "U4") (pin "68") (pinfunction "GND_68") (pintype "bidirectional"))
      (node (ref "U4") (pin "77") (pinfunction "GND_77") (pintype "bidirectional"))
      (node (ref "U4") (pin "91") (pinfunction "GND_91") (pintype "bidirectional"))
      (node (ref "U4") (pin "96") (pinfunction "GND_96") (pintype "bidirectional"))
      (node (ref "U5") (pin "4") (pinfunction "VSS_4") (pintype "bidirectional"))
      (node (ref "U6") (pin "5") (pinfunction "GND_5") (pintype "bidirectional"))
      (node (ref "U6") (pin "P$1") (pinfunction "GND_P$1") (pintype "bidirectional"))
      (node (ref "U6") (pin "P$2") (pinfunction "GND_P$2") (pintype "bidirectional"))
      (node (ref "U6") (pin "P$3") (pinfunction "GND_P$3") (pintype "bidirectional"))
      (node (ref "U6") (pin "P$4") (pinfunction "GND_P$4") (pintype "bidirectional"))
      (node (ref "U7") (pin "5") (pinfunction "GND_5") (pintype "bidirectional"))
      (node (ref "U7") (pin "P$1") (pinfunction "GND_P$1") (pintype "bidirectional"))
      (node (ref "U7") (pin "P$2") (pinfunction "GND_P$2") (pintype "bidirectional"))
      (node (ref "U7") (pin "P$3") (pinfunction "GND_P$3") (pintype "bidirectional"))
      (node (ref "U7") (pin "P$4") (pinfunction "GND_P$4") (pintype "bidirectional"))
      (node (ref "U8") (pin "5") (pinfunction "GND_5") (pintype "bidirectional"))
      (node (ref "U8") (pin "P$1") (pinfunction "GND_P$1") (pintype "bidirectional"))
      (node (ref "U8") (pin "P$2") (pinfunction "GND_P$2") (pintype "bidirectional"))
      (node (ref "U8") (pin "P$3") (pinfunction "GND_P$3") (pintype "bidirectional"))
      (node (ref "U8") (pin "P$4") (pinfunction "GND_P$4") (pintype "bidirectional"))
      (node (ref "U9") (pin "18") (pinfunction "GND_18") (pintype "bidirectional"))
      (node (ref "U9") (pin "21") (pinfunction "GND_21") (pintype "bidirectional"))
      (node (ref "U9") (pin "25") (pinfunction "AGND_25") (pintype "bidirectional"))
      (node (ref "U9") (pin "26") (pinfunction "TEST_26") (pintype "bidirectional"))
      (node (ref "U9") (pin "7") (pinfunction "GND_7") (pintype "bidirectional"))
      (node (ref "X2") (pin "2") (pinfunction "GND_2") (pintype "bidirectional"))
      (node (ref "X3") (pin "2") (pinfunction "GND_2") (pintype "bidirectional"))
    )
    (net (code "60") (name "INIT_B") (class "Default")
      (node (ref "U1") (pin "58") (pinfunction "PF3_ADC3_58") (pintype "bidirectional"))
      (node (ref "U4") (pin "39") (pinfunction "IO_L65P_INIT_B_2_39") (pintype "bidirectional"))
    )
    (net (code "61") (name "JTAG_TCK") (class "Default")
      (node (ref "U1") (pin "57") (pinfunction "PF4_ADC4/TCK_57") (pintype "bidirectional"))
      (node (ref "U4") (pin "109") (pinfunction "TCK_109") (pintype "bidirectional"))
    )
    (net (code "62") (name "JTAG_TDI") (class "Default")
      (node (ref "U1") (pin "55") (pinfunction "PF6_ADC6/TDO_55") (pintype "bidirectional"))
      (node (ref "U4") (pin "110") (pinfunction "TDI_110") (pintype "bidirectional"))
    )
    (net (code "63") (name "JTAG_TDO") (class "Default")
      (node (ref "U1") (pin "56") (pinfunction "PF5_ADC5/TMS_56") (pintype "bidirectional"))
      (node (ref "U4") (pin "106") (pinfunction "TDO_106") (pintype "bidirectional"))
    )
    (net (code "64") (name "JTAG_TMS") (class "Default")
      (node (ref "U1") (pin "54") (pinfunction "PF7_ADC7/TDI_54") (pintype "bidirectional"))
      (node (ref "U4") (pin "107") (pinfunction "TMS_107") (pintype "bidirectional"))
    )
    (net (code "65") (name "MCU_FLASH_CE") (class "Default")
      (node (ref "R2") (pin "2") (pinfunction "2_2") (pintype "bidirectional"))
      (node (ref "U1") (pin "14") (pinfunction "PB4_OC0_14") (pintype "bidirectional"))
      (node (ref "U2") (pin "1") (pinfunction "CE_1") (pintype "bidirectional"))
    )
    (net (code "66") (name "MCU_GPIO_0") (class "Default")
      (node (ref "J2") (pin "1") (pinfunction "1_1") (pintype "bidirectional"))
      (node (ref "U1") (pin "17") (pinfunction "PB7_OC2/OC1C_17") (pintype "bidirectional"))
    )
    (net (code "67") (name "MCU_GPIO_1") (class "Default")
      (node (ref "J2") (pin "2") (pinfunction "2_2") (pintype "bidirectional"))
      (node (ref "U1") (pin "18") (pinfunction "PG3_TOSC2_18") (pintype "bidirectional"))
    )
    (net (code "68") (name "MCU_GPIO_2") (class "Default")
      (node (ref "J2") (pin "3") (pinfunction "3_3") (pintype "bidirectional"))
      (node (ref "U1") (pin "19") (pinfunction "PG4_TOSC2_19") (pintype "bidirectional"))
    )
    (net (code "69") (name "MCU_GPIO_3") (class "Default")
      (node (ref "J2") (pin "4") (pinfunction "4_4") (pintype "bidirectional"))
      (node (ref "U1") (pin "16") (pinfunction "PB6_OC1B_16") (pintype "bidirectional"))
    )
    (net (code "70") (name "MCU_LED0") (class "Default")
      (node (ref "R3") (pin "1") (pinfunction "1_1") (pintype "bidirectional"))
      (node (ref "U1") (pin "32") (pinfunction "PD7_T2_32") (pintype "bidirectional"))
    )
    (net (code "71") (name "MCU_LED1") (class "Default")
      (node (ref "R4") (pin "1") (pinfunction "1_1") (pintype "bidirectional"))
      (node (ref "U1") (pin "31") (pinfunction "PD6_T1_31") (pintype "bidirectional"))
    )
    (net (code "72") (name "MCU_LED2") (class "Default")
      (node (ref "R5") (pin "1") (pinfunction "1_1") (pintype "bidirectional"))
      (node (ref "U1") (pin "30") (pinfunction "PD5_XCK1_30") (pintype "bidirectional"))
    )
    (net (code "73") (name "MCU_LED3") (class "Default")
      (node (ref "R6") (pin "1") (pinfunction "1_1") (pintype "bidirectional"))
      (node (ref "U1") (pin "29") (pinfunction "PD4_ICP1_29") (pintype "bidirectional"))
    )
    (net (code "74") (name "MCU_MISO") (class "Default")
      (node (ref "U1") (pin "13") (pinfunction "PB3_MISO_13") (pintype "bidirectional"))
      (node (ref "U2") (pin "2") (pinfunction "SO_2") (pintype "bidirectional"))
      (node (ref "U3") (pin "7") (pinfunction "SDO_7") (pintype "bidirectional"))
    )
    (net (code "75") (name "MCU_MOSI") (class "Default")
      (node (ref "U1") (pin "12") (pinfunction "PB2_MOSI_12") (pintype "bidirectional"))
      (node (ref "U2") (pin "5") (pinfunction "SI_5") (pintype "bidirectional"))
      (node (ref "U3") (pin "5") (pinfunction "SDI_5") (pintype "bidirectional"))
    )
    (net (code "76") (name "MCU_RESET") (class "Default")
      (node (ref "J1") (pin "5") (pinfunction "RST_5") (pintype "bidirectional"))
      (node (ref "R7") (pin "1") (pinfunction "1_1") (pintype "bidirectional"))
      (node (ref "S1") (pin "2") (pinfunction "3_2") (pintype "bidirectional"))
      (node (ref "U1") (pin "20") (pinfunction "_RESET_20") (pintype "bidirectional"))
    )
    (net (code "77") (name "MCU_RX0{slash}PDI") (class "Default")
      (node (ref "J1") (pin "4") (pinfunction "MOSI_4") (pintype "bidirectional"))
      (node (ref "U1") (pin "2") (pinfunction "PE0_RXD0/PDI_2") (pintype "bidirectional"))
    )
    (net (code "78") (name "MCU_RX1") (class "Default")
      (node (ref "U1") (pin "27") (pinfunction "PD2_RXD1/INT2_27") (pintype "bidirectional"))
      (node (ref "U9") (pin "1") (pinfunction "TXD_1") (pintype "bidirectional"))
    )
    (net (code "79") (name "MCU_SCK") (class "Default")
      (node (ref "J1") (pin "3") (pinfunction "SCK_3") (pintype "bidirectional"))
      (node (ref "U1") (pin "11") (pinfunction "PB1_SCK_11") (pintype "bidirectional"))
      (node (ref "U2") (pin "6") (pinfunction "SCK_6") (pintype "bidirectional"))
      (node (ref "U3") (pin "6") (pinfunction "SCK_6") (pintype "bidirectional"))
    )
    (net (code "80") (name "MCU_TX0{slash}PDO") (class "Default")
      (node (ref "J1") (pin "1") (pinfunction "MISO_1") (pintype "bidirectional"))
      (node (ref "U1") (pin "3") (pinfunction "PE1_TXD0/PDO_3") (pintype "bidirectional"))
    )
    (net (code "81") (name "MCU_TX1") (class "Default")
      (node (ref "U1") (pin "28") (pinfunction "PD3_TXD1/INT3_28") (pintype "bidirectional"))
      (node (ref "U9") (pin "5") (pinfunction "RXD_5") (pintype "bidirectional"))
    )
    (net (code "82") (name "MCU_VCC") (class "Default")
      (node (ref "R1") (pin "1") (pinfunction "1_1") (pintype "bidirectional"))
      (node (ref "R2") (pin "1") (pinfunction "1_1") (pintype "bidirectional"))
      (node (ref "R22") (pin "1") (pinfunction "1_1") (pintype "bidirectional"))
      (node (ref "R7") (pin "2") (pinfunction "2_2") (pintype "bidirectional"))
      (node (ref "U1") (pin "21") (pinfunction "VCC_21") (pintype "bidirectional"))
      (node (ref "U1") (pin "52") (pinfunction "VCC_52") (pintype "bidirectional"))
      (node (ref "U1") (pin "62") (pinfunction "AVREF_62") (pintype "bidirectional"))
      (node (ref "U1") (pin "64") (pinfunction "AVCC_64") (pintype "bidirectional"))
      (node (ref "U2") (pin "3") (pinfunction "WP_3") (pintype "bidirectional"))
      (node (ref "U2") (pin "7") (pinfunction "HOLD_7") (pintype "bidirectional"))
      (node (ref "U2") (pin "8") (pinfunction "VDD_8") (pintype "bidirectional"))
      (node (ref "U8") (pin "4") (pinfunction "SENSE2-_4") (pintype "bidirectional"))
    )
    (net (code "83") (name "MODE0") (class "Default")
      (node (ref "R12") (pin "2") (pinfunction "2_2") (pintype "bidirectional"))
      (node (ref "S3") (pin "1") (pinfunction "1X_1") (pintype "bidirectional"))
      (node (ref "U4") (pin "69") (pinfunction "IO_L1N_M0_CMPMISO_2_69") (pintype "bidirectional"))
    )
    (net (code "84") (name "MODE1") (class "Default")
      (node (ref "R13") (pin "2") (pinfunction "2_2") (pintype "bidirectional"))
      (node (ref "S3") (pin "2") (pinfunction "2X_2") (pintype "bidirectional"))
      (node (ref "U4") (pin "60") (pinfunction "IO_L13P_M1_2_60") (pintype "bidirectional"))
    )
    (net (code "85") (name "MONITORING") (class "Default")
      (node (ref "S3") (pin "4") (pinfunction "4X_4") (pintype "bidirectional"))
      (node (ref "U11") (pin "1") (pinfunction "PE6(INT6/AIN0)_1") (pintype "bidirectional"))
    )
    (net (code "86") (name "MON_HWB") (class "Default")
      (node (ref "15K") (pin "1") (pinfunction "1_1") (pintype "bidirectional"))
      (node (ref "J6") (pin "1") (pinfunction "1_1") (pintype "bidirectional"))
      (node (ref "U11") (pin "33") (pinfunction "PE2(HWB)_33") (pintype "bidirectional"))
    )
    (net (code "87") (name "MON_MISO") (class "Default")
      (node (ref "J10") (pin "1") (pinfunction "MISO_1") (pintype "bidirectional"))
      (node (ref "U11") (pin "11") (pinfunction "PB3(PDO/PCINT3/MISO)_11") (pintype "bidirectional"))
    )
    (net (code "88") (name "MON_MOSI") (class "Default")
      (node (ref "J10") (pin "4") (pinfunction "MOSI_4") (pintype "bidirectional"))
      (node (ref "U11") (pin "10") (pinfunction "PB2(PDI/PCINT2/MOSI)_10") (pintype "bidirectional"))
    )
    (net (code "89") (name "MON_RESET") (class "Default")
      (node (ref "J10") (pin "5") (pinfunction "RST_5") (pintype "bidirectional"))
      (node (ref "R35") (pin "1") (pinfunction "1_1") (pintype "bidirectional"))
      (node (ref "S4") (pin "2") (pinfunction "3_2") (pintype "bidirectional"))
      (node (ref "U11") (pin "13") (pinfunction "_RESET_13") (pintype "bidirectional"))
    )
    (net (code "90") (name "MON_SCK") (class "Default")
      (node (ref "J10") (pin "3") (pinfunction "SCK_3") (pintype "bidirectional"))
      (node (ref "U11") (pin "9") (pinfunction "PB1(PCINT1/SCL)_9") (pintype "bidirectional"))
    )
    (net (code "91") (name "MON_VCC") (class "Default")
      (node (ref "15K") (pin "2") (pinfunction "2_2") (pintype "bidirectional"))
      (node (ref "J10") (pin "2") (pinfunction "VCC_2") (pintype "bidirectional"))
      (node (ref "R16") (pin "1") (pinfunction "1_1") (pintype "bidirectional"))
      (node (ref "R35") (pin "2") (pinfunction "2_2") (pintype "bidirectional"))
      (node (ref "U11") (pin "14") (pinfunction "VCC_14") (pintype "bidirectional"))
      (node (ref "U11") (pin "24") (pinfunction "AVCC_24") (pintype "bidirectional"))
      (node (ref "U11") (pin "34") (pinfunction "VCC_34") (pintype "bidirectional"))
      (node (ref "U11") (pin "44") (pinfunction "AVCC_44") (pintype "bidirectional"))
      (node (ref "U6") (pin "10") (pinfunction "VDD_10") (pintype "bidirectional"))
      (node (ref "U6") (pin "4") (pinfunction "SENSE2-_4") (pintype "bidirectional"))
      (node (ref "U7") (pin "10") (pinfunction "VDD_10") (pintype "bidirectional"))
      (node (ref "U8") (pin "10") (pinfunction "VDD_10") (pintype "bidirectional"))
    )
    (net (code "92") (name "Net-(C28-P$1)") (class "Default")
      (node (ref "C28") (pin "1") (pinfunction "P$1_1") (pintype "bidirectional"))
      (node (ref "U9") (pin "17") (pinfunction "3V3OUT_17") (pintype "bidirectional"))
    )
    (net (code "93") (name "Net-(C32-P$1)") (class "Default")
      (node (ref "C32") (pin "1") (pinfunction "P$1_1") (pintype "bidirectional"))
      (node (ref "U11") (pin "6") (pinfunction "UCAP_6") (pintype "bidirectional"))
    )
    (net (code "94") (name "Net-(C33-P$1)") (class "Default")
      (node (ref "C33") (pin "1") (pinfunction "P$1_1") (pintype "bidirectional"))
      (node (ref "U11") (pin "17") (pinfunction "XTAL1_17") (pintype "bidirectional"))
      (node (ref "X4") (pin "1") (pinfunction "P$1_1") (pintype "bidirectional"))
    )
    (net (code "95") (name "Net-(C34-P$1)") (class "Default")
      (node (ref "C34") (pin "1") (pinfunction "P$1_1") (pintype "bidirectional"))
      (node (ref "U11") (pin "16") (pinfunction "XTAL2_16") (pintype "bidirectional"))
      (node (ref "X4") (pin "3") (pinfunction "P$2_3") (pintype "bidirectional"))
    )
    (net (code "96") (name "Net-(C35-P$1)") (class "Default")
      (node (ref "C35") (pin "1") (pinfunction "P$1_1") (pintype "bidirectional"))
      (node (ref "U1") (pin "23") (pinfunction "XTAL2_23") (pintype "bidirectional"))
      (node (ref "X1") (pin "3") (pinfunction "P$2_3") (pintype "bidirectional"))
    )
    (net (code "97") (name "Net-(C36-P$1)") (class "Default")
      (node (ref "C36") (pin "1") (pinfunction "P$1_1") (pintype "bidirectional"))
      (node (ref "U1") (pin "24") (pinfunction "XTAL1_24") (pintype "bidirectional"))
      (node (ref "X1") (pin "1") (pinfunction "P$1_1") (pintype "bidirectional"))
    )
    (net (code "98") (name "Net-(J8-D+)") (class "Default")
      (node (ref "J8") (pin "3") (pinfunction "D+_3") (pintype "bidirectional"))
      (node (ref "U9") (pin "15") (pinfunction "USBDP_15") (pintype "bidirectional"))
    )
    (net (code "99") (name "Net-(J8-D-)") (class "Default")
      (node (ref "J8") (pin "2") (pinfunction "D-_2") (pintype "bidirectional"))
      (node (ref "U9") (pin "16") (pinfunction "USBDM_16") (pintype "bidirectional"))
    )
    (net (code "100") (name "Net-(J9-D+)") (class "Default")
      (node (ref "J9") (pin "3") (pinfunction "D+_3") (pintype "bidirectional"))
      (node (ref "R33") (pin "1") (pinfunction "1_1") (pintype "bidirectional"))
    )
    (net (code "101") (name "Net-(J9-D-)") (class "Default")
      (node (ref "J9") (pin "2") (pinfunction "D-_2") (pintype "bidirectional"))
      (node (ref "R34") (pin "1") (pinfunction "1_1") (pintype "bidirectional"))
    )
    (net (code "102") (name "Net-(L2-P$2)") (class "Default")
      (node (ref "L2") (pin "2") (pinfunction "P$2_2") (pintype "bidirectional"))
      (node (ref "U10") (pin "4") (pinfunction "SW1_4") (pintype "bidirectional"))
    )
    (net (code "103") (name "Net-(L3-P$1)") (class "Default")
      (node (ref "L3") (pin "1") (pinfunction "P$1_1") (pintype "bidirectional"))
      (node (ref "U10") (pin "6") (pinfunction "SW2_6") (pintype "bidirectional"))
    )
    (net (code "104") (name "Net-(LED0-Pad1)") (class "Default")
      (node (ref "LED0") (pin "1") (pinfunction "1_1") (pintype "bidirectional"))
      (node (ref "R3") (pin "2") (pinfunction "2_2") (pintype "bidirectional"))
    )
    (net (code "105") (name "Net-(LED1-Pad1)") (class "Default")
      (node (ref "LED1") (pin "1") (pinfunction "1_1") (pintype "bidirectional"))
      (node (ref "R4") (pin "2") (pinfunction "2_2") (pintype "bidirectional"))
    )
    (net (code "106") (name "Net-(LED2-Pad1)") (class "Default")
      (node (ref "LED2") (pin "1") (pinfunction "1_1") (pintype "bidirectional"))
      (node (ref "R5") (pin "2") (pinfunction "2_2") (pintype "bidirectional"))
    )
    (net (code "107") (name "Net-(LED3-Pad1)") (class "Default")
      (node (ref "LED3") (pin "1") (pinfunction "1_1") (pintype "bidirectional"))
      (node (ref "R6") (pin "2") (pinfunction "2_2") (pintype "bidirectional"))
    )
    (net (code "108") (name "Net-(LED4-Pad1)") (class "Default")
      (node (ref "LED4") (pin "1") (pinfunction "1_1") (pintype "bidirectional"))
      (node (ref "R8") (pin "2") (pinfunction "2_2") (pintype "bidirectional"))
    )
    (net (code "109") (name "Net-(LED5-Pad1)") (class "Default")
      (node (ref "LED5") (pin "1") (pinfunction "1_1") (pintype "bidirectional"))
      (node (ref "R9") (pin "2") (pinfunction "2_2") (pintype "bidirectional"))
    )
    (net (code "110") (name "Net-(LED6-Pad1)") (class "Default")
      (node (ref "LED6") (pin "1") (pinfunction "1_1") (pintype "bidirectional"))
      (node (ref "R10") (pin "2") (pinfunction "2_2") (pintype "bidirectional"))
    )
    (net (code "111") (name "Net-(LED7-Pad1)") (class "Default")
      (node (ref "LED7") (pin "1") (pinfunction "1_1") (pintype "bidirectional"))
      (node (ref "R11") (pin "2") (pinfunction "2_2") (pintype "bidirectional"))
    )
    (net (code "112") (name "Net-(PWR-Pad2)") (class "Default")
      (node (ref "PWR") (pin "2") (pinfunction "2_2") (pintype "bidirectional"))
      (node (ref "R32") (pin "2") (pinfunction "2_2") (pintype "bidirectional"))
    )
    (net (code "113") (name "Net-(R26-Pad2)") (class "Default")
      (node (ref "R26") (pin "2") (pinfunction "2_2") (pintype "bidirectional"))
      (node (ref "TX") (pin "2") (pinfunction "2_2") (pintype "bidirectional"))
    )
    (net (code "114") (name "Net-(R27-Pad2)") (class "Default")
      (node (ref "R27") (pin "2") (pinfunction "2_2") (pintype "bidirectional"))
      (node (ref "RX") (pin "2") (pinfunction "2_2") (pintype "bidirectional"))
    )
    (net (code "115") (name "Net-(U6-ADDR_SEL)") (class "Default")
      (node (ref "R20") (pin "2") (pinfunction "2_2") (pintype "bidirectional"))
      (node (ref "U6") (pin "6") (pinfunction "ADDR_SEL_6") (pintype "bidirectional"))
    )
    (net (code "116") (name "Net-(U7-ADDR_SEL)") (class "Default")
      (node (ref "R21") (pin "2") (pinfunction "2_2") (pintype "bidirectional"))
      (node (ref "U7") (pin "6") (pinfunction "ADDR_SEL_6") (pintype "bidirectional"))
    )
    (net (code "117") (name "Net-(U8-ADDR_SEL)") (class "Default")
      (node (ref "R23") (pin "2") (pinfunction "2_2") (pintype "bidirectional"))
      (node (ref "U8") (pin "6") (pinfunction "ADDR_SEL_6") (pintype "bidirectional"))
    )
    (net (code "118") (name "Net-(U9-CBUS2)") (class "Default")
      (node (ref "R26") (pin "1") (pinfunction "1_1") (pintype "bidirectional"))
      (node (ref "U9") (pin "13") (pinfunction "CBUS2_13") (pintype "bidirectional"))
    )
    (net (code "119") (name "Net-(U9-CBUS3)") (class "Default")
      (node (ref "R27") (pin "1") (pinfunction "1_1") (pintype "bidirectional"))
      (node (ref "U9") (pin "14") (pinfunction "CBUS3_14") (pintype "bidirectional"))
    )
    (net (code "120") (name "Net-(U10-VFB1)") (class "Default")
      (node (ref "R28") (pin "2") (pinfunction "2_2") (pintype "bidirectional"))
      (node (ref "R29") (pin "1") (pinfunction "1_1") (pintype "bidirectional"))
      (node (ref "U10") (pin "1") (pinfunction "VFB1_1") (pintype "bidirectional"))
    )
    (net (code "121") (name "Net-(U10-VFB2)") (class "Default")
      (node (ref "R30") (pin "2") (pinfunction "2_2") (pintype "bidirectional"))
      (node (ref "R31") (pin "1") (pinfunction "1_1") (pintype "bidirectional"))
      (node (ref "U10") (pin "8") (pinfunction "VFB2_8") (pintype "bidirectional"))
    )
    (net (code "122") (name "OSC_32") (class "Default")
      (node (ref "U4") (pin "94") (pinfunction "IO_L40N_GCLK10_1_94") (pintype "bidirectional"))
      (node (ref "X3") (pin "3") (pinfunction "OUTPUT_3") (pintype "bidirectional"))
    )
    (net (code "123") (name "OSC_50") (class "Default")
      (node (ref "U4") (pin "51") (pinfunction "IO_L31P_GCLK31_D14_2_51") (pintype "bidirectional"))
      (node (ref "X2") (pin "3") (pinfunction "OUTPUT_3") (pintype "bidirectional"))
    )
    (net (code "124") (name "RD") (class "Default")
      (node (ref "U1") (pin "34") (pinfunction "PG1_RD#_34") (pintype "bidirectional"))
      (node (ref "U4") (pin "84") (pinfunction "IO_L43N_GCLK4_1_84") (pintype "bidirectional"))
    )
    (net (code "125") (name "SCL") (class "Default")
      (node (ref "R24") (pin "1") (pinfunction "1_1") (pintype "bidirectional"))
      (node (ref "U11") (pin "18") (pinfunction "PD0(OC0B/SCL/INT0)_18") (pintype "bidirectional"))
      (node (ref "U6") (pin "9") (pinfunction "SMCLK_9") (pintype "bidirectional"))
      (node (ref "U7") (pin "9") (pinfunction "SMCLK_9") (pintype "bidirectional"))
      (node (ref "U8") (pin "9") (pinfunction "SMCLK_9") (pintype "bidirectional"))
    )
    (net (code "126") (name "SDA") (class "Default")
      (node (ref "R25") (pin "2") (pinfunction "2_2") (pintype "bidirectional"))
      (node (ref "U11") (pin "19") (pinfunction "PD1(SDA/INT1)_19") (pintype "bidirectional"))
      (node (ref "U6") (pin "8") (pinfunction "SMDATA_8") (pintype "bidirectional"))
      (node (ref "U7") (pin "8") (pinfunction "SMDATA_8") (pintype "bidirectional"))
      (node (ref "U8") (pin "8") (pinfunction "SMDATA_8") (pintype "bidirectional"))
    )
    (net (code "127") (name "USB2_VCC") (class "Default")
      (node (ref "J9") (pin "1") (pinfunction "VCC_1") (pintype "bidirectional"))
      (node (ref "U11") (pin "2") (pinfunction "UVCC_2") (pintype "bidirectional"))
      (node (ref "U11") (pin "7") (pinfunction "VBUS_7") (pintype "bidirectional"))
    )
    (net (code "128") (name "USB_VCC") (class "Default")
      (node (ref "C26") (pin "2") (pinfunction "P$2_2") (pintype "bidirectional"))
      (node (ref "C27") (pin "2") (pinfunction "P$2_2") (pintype "bidirectional"))
      (node (ref "L1") (pin "2") (pinfunction "P$2_2") (pintype "bidirectional"))
      (node (ref "R18") (pin "2") (pinfunction "2_2") (pintype "bidirectional"))
      (node (ref "U6") (pin "2") (pinfunction "SENSE1-_2") (pintype "bidirectional"))
    )
    (net (code "129") (name "USB_VCC_RAW") (class "Default")
      (node (ref "C25") (pin "1") (pinfunction "P$1_1") (pintype "bidirectional"))
      (node (ref "J8") (pin "1") (pinfunction "VCC_1") (pintype "bidirectional"))
      (node (ref "L1") (pin "1") (pinfunction "P$1_1") (pintype "bidirectional"))
    )
    (net (code "130") (name "WIRELESS_CS") (class "Default")
      (node (ref "R1") (pin "2") (pinfunction "2_2") (pintype "bidirectional"))
      (node (ref "U1") (pin "60") (pinfunction "PF1_ADC1_60") (pintype "bidirectional"))
      (node (ref "U3") (pin "8") (pinfunction "_CS_8") (pintype "bidirectional"))
    )
    (net (code "131") (name "WIRELESS_INT") (class "Default")
      (node (ref "U1") (pin "61") (pinfunction "PF0_ADC0_61") (pintype "bidirectional"))
      (node (ref "U3") (pin "4") (pinfunction "INT_4") (pintype "bidirectional"))
    )
    (net (code "132") (name "WIRELESS_RESET") (class "Default")
      (node (ref "U1") (pin "15") (pinfunction "PB5_OC1A_15") (pintype "bidirectional"))
      (node (ref "U3") (pin "2") (pinfunction "_RESET_2") (pintype "bidirectional"))
    )
    (net (code "133") (name "WIRELESS_VCC") (class "Default")
      (node (ref "R36") (pin "2") (pinfunction "2_2") (pintype "bidirectional"))
      (node (ref "U3") (pin "10") (pinfunction "VI_10") (pintype "bidirectional"))
      (node (ref "U8") (pin "2") (pinfunction "SENSE1-_2") (pintype "bidirectional"))
    )
    (net (code "134") (name "WIRELESS_WAKE") (class "Default")
      (node (ref "U1") (pin "4") (pinfunction "PE2_XCK0/AIN0_4") (pintype "bidirectional"))
      (node (ref "U3") (pin "3") (pinfunction "WAKE_3") (pintype "bidirectional"))
    )
    (net (code "135") (name "WR") (class "Default")
      (node (ref "U1") (pin "33") (pinfunction "PG0_WR#_33") (pintype "bidirectional"))
      (node (ref "U4") (pin "85") (pinfunction "IO_L43P_GCLK5_1_85") (pintype "bidirectional"))
    )
    (net (code "136") (name "unconnected-(J8-SHIELD-PadCASE_1)") (class "Default")
      (node (ref "J8") (pin "CASE_1") (pinfunction "SHIELD_CASE_1") (pintype "bidirectional"))
    )
    (net (code "137") (name "unconnected-(J9-SHIELD-PadCASE_1)") (class "Default")
      (node (ref "J9") (pin "CASE_1") (pinfunction "SHIELD_CASE_1") (pintype "bidirectional"))
    )
    (net (code "138") (name "unconnected-(U1-PB0_SS#-Pad10)") (class "Default")
      (node (ref "U1") (pin "10") (pinfunction "PB0_SS#_10") (pintype "bidirectional"))
    )
    (net (code "139") (name "unconnected-(U1-PE4_OC3B{slash}INT4-Pad6)") (class "Default")
      (node (ref "U1") (pin "6") (pinfunction "PE4_OC3B/INT4_6") (pintype "bidirectional"))
    )
    (net (code "140") (name "unconnected-(U1-_PEN-Pad1)") (class "Default")
      (node (ref "U1") (pin "1") (pinfunction "_PEN_1") (pintype "bidirectional"))
    )
    (net (code "141") (name "unconnected-(U4-CMPCS_B_2-Pad72)") (class "Default")
      (node (ref "U4") (pin "72") (pinfunction "CMPCS_B_2_72") (pintype "bidirectional"))
    )
    (net (code "142") (name "unconnected-(U4-IO_L1N_VREF_0-Pad143)") (class "Default")
      (node (ref "U4") (pin "143") (pinfunction "IO_L1N_VREF_0_143") (pintype "bidirectional"))
    )
    (net (code "143") (name "unconnected-(U4-IO_L1N_VREF_3-Pad34)") (class "Default")
      (node (ref "U4") (pin "34") (pinfunction "IO_L1N_VREF_3_34") (pintype "bidirectional"))
    )
    (net (code "144") (name "unconnected-(U4-IO_L1P_3-Pad35)") (class "Default")
      (node (ref "U4") (pin "35") (pinfunction "IO_L1P_3_35") (pintype "bidirectional"))
    )
    (net (code "145") (name "unconnected-(U4-IO_L1P_HSWAPEN_0-Pad144)") (class "Default")
      (node (ref "U4") (pin "144") (pinfunction "IO_L1P_HSWAPEN_0_144") (pintype "bidirectional"))
    )
    (net (code "146") (name "unconnected-(U4-IO_L2N_0-Pad141)") (class "Default")
      (node (ref "U4") (pin "141") (pinfunction "IO_L2N_0_141") (pintype "bidirectional"))
    )
    (net (code "147") (name "unconnected-(U4-IO_L2N_3-Pad32)") (class "Default")
      (node (ref "U4") (pin "32") (pinfunction "IO_L2N_3_32") (pintype "bidirectional"))
    )
    (net (code "148") (name "unconnected-(U4-IO_L2P_0-Pad142)") (class "Default")
      (node (ref "U4") (pin "142") (pinfunction "IO_L2P_0_142") (pintype "bidirectional"))
    )
    (net (code "149") (name "unconnected-(U4-IO_L2P_3-Pad33)") (class "Default")
      (node (ref "U4") (pin "33") (pinfunction "IO_L2P_3_33") (pintype "bidirectional"))
    )
    (net (code "150") (name "unconnected-(U4-IO_L2P_CMPCLK_2-Pad67)") (class "Default")
      (node (ref "U4") (pin "67") (pinfunction "IO_L2P_CMPCLK_2_67") (pintype "bidirectional"))
    )
    (net (code "151") (name "unconnected-(U4-IO_L3N_0-Pad139)") (class "Default")
      (node (ref "U4") (pin "139") (pinfunction "IO_L3N_0_139") (pintype "bidirectional"))
    )
    (net (code "152") (name "unconnected-(U4-IO_L3P_0-Pad140)") (class "Default")
      (node (ref "U4") (pin "140") (pinfunction "IO_L3P_0_140") (pintype "bidirectional"))
    )
    (net (code "153") (name "unconnected-(U4-IO_L4N_0-Pad137)") (class "Default")
      (node (ref "U4") (pin "137") (pinfunction "IO_L4N_0_137") (pintype "bidirectional"))
    )
    (net (code "154") (name "unconnected-(U4-IO_L4P_0-Pad138)") (class "Default")
      (node (ref "U4") (pin "138") (pinfunction "IO_L4P_0_138") (pintype "bidirectional"))
    )
    (net (code "155") (name "unconnected-(U4-IO_L13N_D10_2-Pad59)") (class "Default")
      (node (ref "U4") (pin "59") (pinfunction "IO_L13N_D10_2_59") (pintype "bidirectional"))
    )
    (net (code "156") (name "unconnected-(U4-IO_L14N_D12_2-Pad57)") (class "Default")
      (node (ref "U4") (pin "57") (pinfunction "IO_L14N_D12_2_57") (pintype "bidirectional"))
    )
    (net (code "157") (name "unconnected-(U4-IO_L14P_D11_2-Pad58)") (class "Default")
      (node (ref "U4") (pin "58") (pinfunction "IO_L14P_D11_2_58") (pintype "bidirectional"))
    )
    (net (code "158") (name "unconnected-(U4-IO_L30N_GCLK0_USERCCLK_2-Pad55)") (class "Default")
      (node (ref "U4") (pin "55") (pinfunction "IO_L30N_GCLK0_USERCCLK_2_55") (pintype "bidirectional"))
    )
    (net (code "159") (name "unconnected-(U4-IO_L30P_GCLK1_D13_2-Pad56)") (class "Default")
      (node (ref "U4") (pin "56") (pinfunction "IO_L30P_GCLK1_D13_2_56") (pintype "bidirectional"))
    )
    (net (code "160") (name "unconnected-(U4-IO_L31N_GCLK30_D15_2-Pad50)") (class "Default")
      (node (ref "U4") (pin "50") (pinfunction "IO_L31N_GCLK30_D15_2_50") (pintype "bidirectional"))
    )
    (net (code "161") (name "unconnected-(U4-IO_L33N_1-Pad99)") (class "Default")
      (node (ref "U4") (pin "99") (pinfunction "IO_L33N_1_99") (pintype "bidirectional"))
    )
    (net (code "162") (name "unconnected-(U4-IO_L33P_1-Pad100)") (class "Default")
      (node (ref "U4") (pin "100") (pinfunction "IO_L33P_1_100") (pintype "bidirectional"))
    )
    (net (code "163") (name "unconnected-(U4-IO_L34N_1-Pad97)") (class "Default")
      (node (ref "U4") (pin "97") (pinfunction "IO_L34N_1_97") (pintype "bidirectional"))
    )
    (net (code "164") (name "unconnected-(U4-IO_L34N_GCLK18_0-Pad133)") (class "Default")
      (node (ref "U4") (pin "133") (pinfunction "IO_L34N_GCLK18_0_133") (pintype "bidirectional"))
    )
    (net (code "165") (name "unconnected-(U4-IO_L34P_1-Pad98)") (class "Default")
      (node (ref "U4") (pin "98") (pinfunction "IO_L34P_1_98") (pintype "bidirectional"))
    )
    (net (code "166") (name "unconnected-(U4-IO_L34P_GCLK19_0-Pad134)") (class "Default")
      (node (ref "U4") (pin "134") (pinfunction "IO_L34P_GCLK19_0_134") (pintype "bidirectional"))
    )
    (net (code "167") (name "unconnected-(U4-IO_L35N_GCLK16_0-Pad131)") (class "Default")
      (node (ref "U4") (pin "131") (pinfunction "IO_L35N_GCLK16_0_131") (pintype "bidirectional"))
    )
    (net (code "168") (name "unconnected-(U4-IO_L35P_GCLK17_0-Pad132)") (class "Default")
      (node (ref "U4") (pin "132") (pinfunction "IO_L35P_GCLK17_0_132") (pintype "bidirectional"))
    )
    (net (code "169") (name "unconnected-(U4-IO_L36N_3-Pad29)") (class "Default")
      (node (ref "U4") (pin "29") (pinfunction "IO_L36N_3_29") (pintype "bidirectional"))
    )
    (net (code "170") (name "unconnected-(U4-IO_L36N_GCLK14_0-Pad126)") (class "Default")
      (node (ref "U4") (pin "126") (pinfunction "IO_L36N_GCLK14_0_126") (pintype "bidirectional"))
    )
    (net (code "171") (name "unconnected-(U4-IO_L36P_3-Pad30)") (class "Default")
      (node (ref "U4") (pin "30") (pinfunction "IO_L36P_3_30") (pintype "bidirectional"))
    )
    (net (code "172") (name "unconnected-(U4-IO_L36P_GCLK15_0-Pad127)") (class "Default")
      (node (ref "U4") (pin "127") (pinfunction "IO_L36P_GCLK15_0_127") (pintype "bidirectional"))
    )
    (net (code "173") (name "unconnected-(U4-IO_L37N_GCLK12_0-Pad123)") (class "Default")
      (node (ref "U4") (pin "123") (pinfunction "IO_L37N_GCLK12_0_123") (pintype "bidirectional"))
    )
    (net (code "174") (name "unconnected-(U4-IO_L37P_GCLK13_0-Pad124)") (class "Default")
      (node (ref "U4") (pin "124") (pinfunction "IO_L37P_GCLK13_0_124") (pintype "bidirectional"))
    )
    (net (code "175") (name "unconnected-(U4-IO_L40P_GCLK11_1-Pad95)") (class "Default")
      (node (ref "U4") (pin "95") (pinfunction "IO_L40P_GCLK11_1_95") (pintype "bidirectional"))
    )
    (net (code "176") (name "unconnected-(U4-IO_L41N_GCLK8_1-Pad92)") (class "Default")
      (node (ref "U4") (pin "92") (pinfunction "IO_L41N_GCLK8_1_92") (pintype "bidirectional"))
    )
    (net (code "177") (name "unconnected-(U4-IO_L41P_GCLK9_IRDY1_1-Pad93)") (class "Default")
      (node (ref "U4") (pin "93") (pinfunction "IO_L41P_GCLK9_IRDY1_1_93") (pintype "bidirectional"))
    )
    (net (code "178") (name "unconnected-(U4-IO_L42N_GCLK6_TRDY1_1-Pad87)") (class "Default")
      (node (ref "U4") (pin "87") (pinfunction "IO_L42N_GCLK6_TRDY1_1_87") (pintype "bidirectional"))
    )
    (net (code "179") (name "unconnected-(U4-IO_L42P_GCLK7_1-Pad88)") (class "Default")
      (node (ref "U4") (pin "88") (pinfunction "IO_L42P_GCLK7_1_88") (pintype "bidirectional"))
    )
    (net (code "180") (name "unconnected-(U4-IO_L62N_VREF_0-Pad120)") (class "Default")
      (node (ref "U4") (pin "120") (pinfunction "IO_L62N_VREF_0_120") (pintype "bidirectional"))
    )
    (net (code "181") (name "unconnected-(U4-IO_L62P_0-Pad121)") (class "Default")
      (node (ref "U4") (pin "121") (pinfunction "IO_L62P_0_121") (pintype "bidirectional"))
    )
    (net (code "182") (name "unconnected-(U4-IO_L63N_SCP6_0-Pad118)") (class "Default")
      (node (ref "U4") (pin "118") (pinfunction "IO_L63N_SCP6_0_118") (pintype "bidirectional"))
    )
    (net (code "183") (name "unconnected-(U4-IO_L63P_SCP7_0-Pad119)") (class "Default")
      (node (ref "U4") (pin "119") (pinfunction "IO_L63P_SCP7_0_119") (pintype "bidirectional"))
    )
    (net (code "184") (name "unconnected-(U4-IO_L64N_D9_2-Pad40)") (class "Default")
      (node (ref "U4") (pin "40") (pinfunction "IO_L64N_D9_2_40") (pintype "bidirectional"))
    )
    (net (code "185") (name "unconnected-(U4-IO_L64N_SCP4_0-Pad116)") (class "Default")
      (node (ref "U4") (pin "116") (pinfunction "IO_L64N_SCP4_0_116") (pintype "bidirectional"))
    )
    (net (code "186") (name "unconnected-(U4-IO_L64P_D8_2-Pad41)") (class "Default")
      (node (ref "U4") (pin "41") (pinfunction "IO_L64P_D8_2_41") (pintype "bidirectional"))
    )
    (net (code "187") (name "unconnected-(U4-IO_L64P_SCP5_0-Pad117)") (class "Default")
      (node (ref "U4") (pin "117") (pinfunction "IO_L64P_SCP5_0_117") (pintype "bidirectional"))
    )
    (net (code "188") (name "unconnected-(U4-IO_L65N_SCP2_0-Pad114)") (class "Default")
      (node (ref "U4") (pin "114") (pinfunction "IO_L65N_SCP2_0_114") (pintype "bidirectional"))
    )
    (net (code "189") (name "unconnected-(U4-IO_L65P_SCP3_0-Pad115)") (class "Default")
      (node (ref "U4") (pin "115") (pinfunction "IO_L65P_SCP3_0_115") (pintype "bidirectional"))
    )
    (net (code "190") (name "unconnected-(U4-IO_L66N_SCP0_0-Pad111)") (class "Default")
      (node (ref "U4") (pin "111") (pinfunction "IO_L66N_SCP0_0_111") (pintype "bidirectional"))
    )
    (net (code "191") (name "unconnected-(U4-IO_L66P_SCP1_0-Pad112)") (class "Default")
      (node (ref "U4") (pin "112") (pinfunction "IO_L66P_SCP1_0_112") (pintype "bidirectional"))
    )
    (net (code "192") (name "unconnected-(U6-ALERT#-Pad7)") (class "Default")
      (node (ref "U6") (pin "7") (pinfunction "ALERT#_7") (pintype "bidirectional"))
    )
    (net (code "193") (name "unconnected-(U7-ALERT#-Pad7)") (class "Default")
      (node (ref "U7") (pin "7") (pinfunction "ALERT#_7") (pintype "bidirectional"))
    )
    (net (code "194") (name "unconnected-(U8-ALERT#-Pad7)") (class "Default")
      (node (ref "U8") (pin "7") (pinfunction "ALERT#_7") (pintype "bidirectional"))
    )
    (net (code "195") (name "unconnected-(U9-CBUS0-Pad23)") (class "Default")
      (node (ref "U9") (pin "23") (pinfunction "CBUS0_23") (pintype "bidirectional"))
    )
    (net (code "196") (name "unconnected-(U9-CBUS1-Pad22)") (class "Default")
      (node (ref "U9") (pin "22") (pinfunction "CBUS1_22") (pintype "bidirectional"))
    )
    (net (code "197") (name "unconnected-(U9-CBUS4-Pad12)") (class "Default")
      (node (ref "U9") (pin "12") (pinfunction "CBUS4_12") (pintype "bidirectional"))
    )
    (net (code "198") (name "unconnected-(U9-CTS#-Pad11)") (class "Default")
      (node (ref "U9") (pin "11") (pinfunction "CTS#_11") (pintype "bidirectional"))
    )
    (net (code "199") (name "unconnected-(U9-DCD#-Pad10)") (class "Default")
      (node (ref "U9") (pin "10") (pinfunction "DCD#_10") (pintype "bidirectional"))
    )
    (net (code "200") (name "unconnected-(U9-DSR#-Pad9)") (class "Default")
      (node (ref "U9") (pin "9") (pinfunction "DSR#_9") (pintype "bidirectional"))
    )
    (net (code "201") (name "unconnected-(U9-DTR#-Pad2)") (class "Default")
      (node (ref "U9") (pin "2") (pinfunction "DTR#_2") (pintype "bidirectional"))
    )
    (net (code "202") (name "unconnected-(U9-OSCI-Pad27)") (class "Default")
      (node (ref "U9") (pin "27") (pinfunction "OSCI_27") (pintype "bidirectional"))
    )
    (net (code "203") (name "unconnected-(U9-OSCO-Pad28)") (class "Default")
      (node (ref "U9") (pin "28") (pinfunction "OSCO_28") (pintype "bidirectional"))
    )
    (net (code "204") (name "unconnected-(U9-RESET#-Pad19)") (class "Default")
      (node (ref "U9") (pin "19") (pinfunction "RESET#_19") (pintype "bidirectional"))
    )
    (net (code "205") (name "unconnected-(U9-RI#-Pad6)") (class "Default")
      (node (ref "U9") (pin "6") (pinfunction "RI#_6") (pintype "bidirectional"))
    )
    (net (code "206") (name "unconnected-(U9-RTS#-Pad3)") (class "Default")
      (node (ref "U9") (pin "3") (pinfunction "RTS#_3") (pintype "bidirectional"))
    )
    (net (code "207") (name "unconnected-(U11-AREF-Pad42)") (class "Default")
      (node (ref "U11") (pin "42") (pinfunction "AREF_42") (pintype "bidirectional"))
    )
    (net (code "208") (name "unconnected-(U11-PB0(SS{slash}PCINT0)-Pad8)") (class "Default")
      (node (ref "U11") (pin "8") (pinfunction "PB0(SS/PCINT0)_8") (pintype "bidirectional"))
    )
    (net (code "209") (name "unconnected-(U11-PB4(PCINT4{slash}ADC11)-Pad28)") (class "Default")
      (node (ref "U11") (pin "28") (pinfunction "PB4(PCINT4/ADC11)_28") (pintype "bidirectional"))
    )
    (net (code "210") (name "unconnected-(U11-PB5(PCINT5(OC1A{slash}OC4B{slash}ADC12)-Pad29)") (class "Default")
      (node (ref "U11") (pin "29") (pinfunction "PB5(PCINT5(OC1A/OC4B/ADC12)_29") (pintype "bidirectional"))
    )
    (net (code "211") (name "unconnected-(U11-PB6(PCINT6{slash}OC1B{slash}OC4B{slash}ADC13)-Pad30)") (class "Default")
      (node (ref "U11") (pin "30") (pinfunction "PB6(PCINT6/OC1B/OC4B/ADC13)_30") (pintype "bidirectional"))
    )
    (net (code "212") (name "unconnected-(U11-PB7(PCINT7{slash}OC0A{slash}OC1C{slash}RTS)-Pad12)") (class "Default")
      (node (ref "U11") (pin "12") (pinfunction "PB7(PCINT7/OC0A/OC1C/RTS)_12") (pintype "bidirectional"))
    )
    (net (code "213") (name "unconnected-(U11-PC6(OC3A{slash}OC4A)-Pad31)") (class "Default")
      (node (ref "U11") (pin "31") (pinfunction "PC6(OC3A/OC4A)_31") (pintype "bidirectional"))
    )
    (net (code "214") (name "unconnected-(U11-PC7(ICP3{slash}CLK0{slash}OC4A)-Pad32)") (class "Default")
      (node (ref "U11") (pin "32") (pinfunction "PC7(ICP3/CLK0/OC4A)_32") (pintype "bidirectional"))
    )
    (net (code "215") (name "unconnected-(U11-PD2(RXD1{slash}INT2)-Pad20)") (class "Default")
      (node (ref "U11") (pin "20") (pinfunction "PD2(RXD1/INT2)_20") (pintype "bidirectional"))
    )
    (net (code "216") (name "unconnected-(U11-PD3(TXD1{slash}INT3)-Pad21)") (class "Default")
      (node (ref "U11") (pin "21") (pinfunction "PD3(TXD1/INT3)_21") (pintype "bidirectional"))
    )
    (net (code "217") (name "unconnected-(U11-PD4(ICP1{slash}ADC8)-Pad25)") (class "Default")
      (node (ref "U11") (pin "25") (pinfunction "PD4(ICP1/ADC8)_25") (pintype "bidirectional"))
    )
    (net (code "218") (name "unconnected-(U11-PD5(XCK1{slash}CTS)-Pad22)") (class "Default")
      (node (ref "U11") (pin "22") (pinfunction "PD5(XCK1/CTS)_22") (pintype "bidirectional"))
    )
    (net (code "219") (name "unconnected-(U11-PD6(T1{slash}OC4D{slash}ADC9)-Pad26)") (class "Default")
      (node (ref "U11") (pin "26") (pinfunction "PD6(T1/OC4D/ADC9)_26") (pintype "bidirectional"))
    )
    (net (code "220") (name "unconnected-(U11-PD7(T0{slash}OC4D{slash}ADC10)-Pad27)") (class "Default")
      (node (ref "U11") (pin "27") (pinfunction "PD7(T0/OC4D/ADC10)_27") (pintype "bidirectional"))
    )
    (net (code "221") (name "unconnected-(U11-PF0(ADC0)-Pad41)") (class "Default")
      (node (ref "U11") (pin "41") (pinfunction "PF0(ADC0)_41") (pintype "bidirectional"))
    )
    (net (code "222") (name "unconnected-(U11-PF1(ADC1)-Pad40)") (class "Default")
      (node (ref "U11") (pin "40") (pinfunction "PF1(ADC1)_40") (pintype "bidirectional"))
    )
    (net (code "223") (name "unconnected-(U11-PF4(ADC4{slash}TCK)-Pad39)") (class "Default")
      (node (ref "U11") (pin "39") (pinfunction "PF4(ADC4/TCK)_39") (pintype "bidirectional"))
    )
    (net (code "224") (name "unconnected-(U11-PF5(ADC5{slash}TMS)-Pad38)") (class "Default")
      (node (ref "U11") (pin "38") (pinfunction "PF5(ADC5/TMS)_38") (pintype "bidirectional"))
    )
    (net (code "225") (name "unconnected-(U11-PF6(ADC6{slash}TDO)-Pad37)") (class "Default")
      (node (ref "U11") (pin "37") (pinfunction "PF6(ADC6/TDO)_37") (pintype "bidirectional"))
    )
    (net (code "226") (name "unconnected-(U11-PF7(ADC7{slash}TDI)-Pad36)") (class "Default")
      (node (ref "U11") (pin "36") (pinfunction "PF7(ADC7/TDI)_36") (pintype "bidirectional"))
    )
  )
)
